# CPU_Logic.net
KiCad netlist of a schematic drawn in Altium Designer
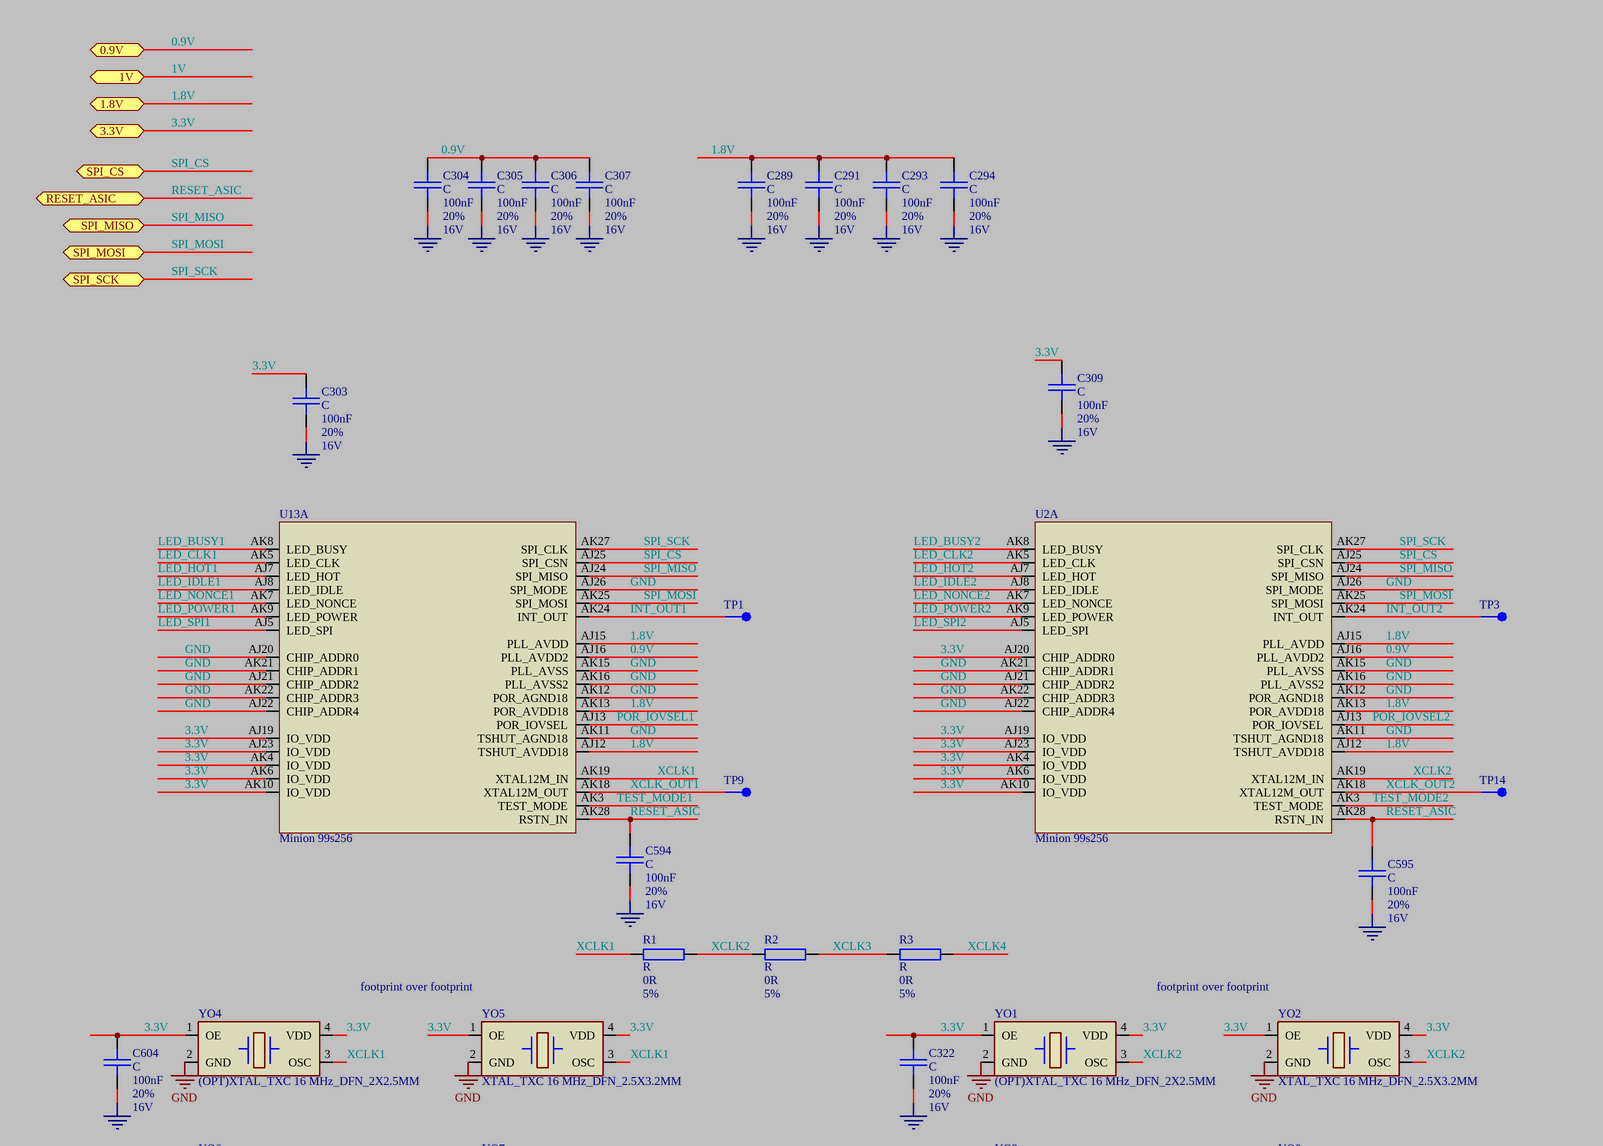
[diagram p0: CPU_Logic.SchDoc, top left]
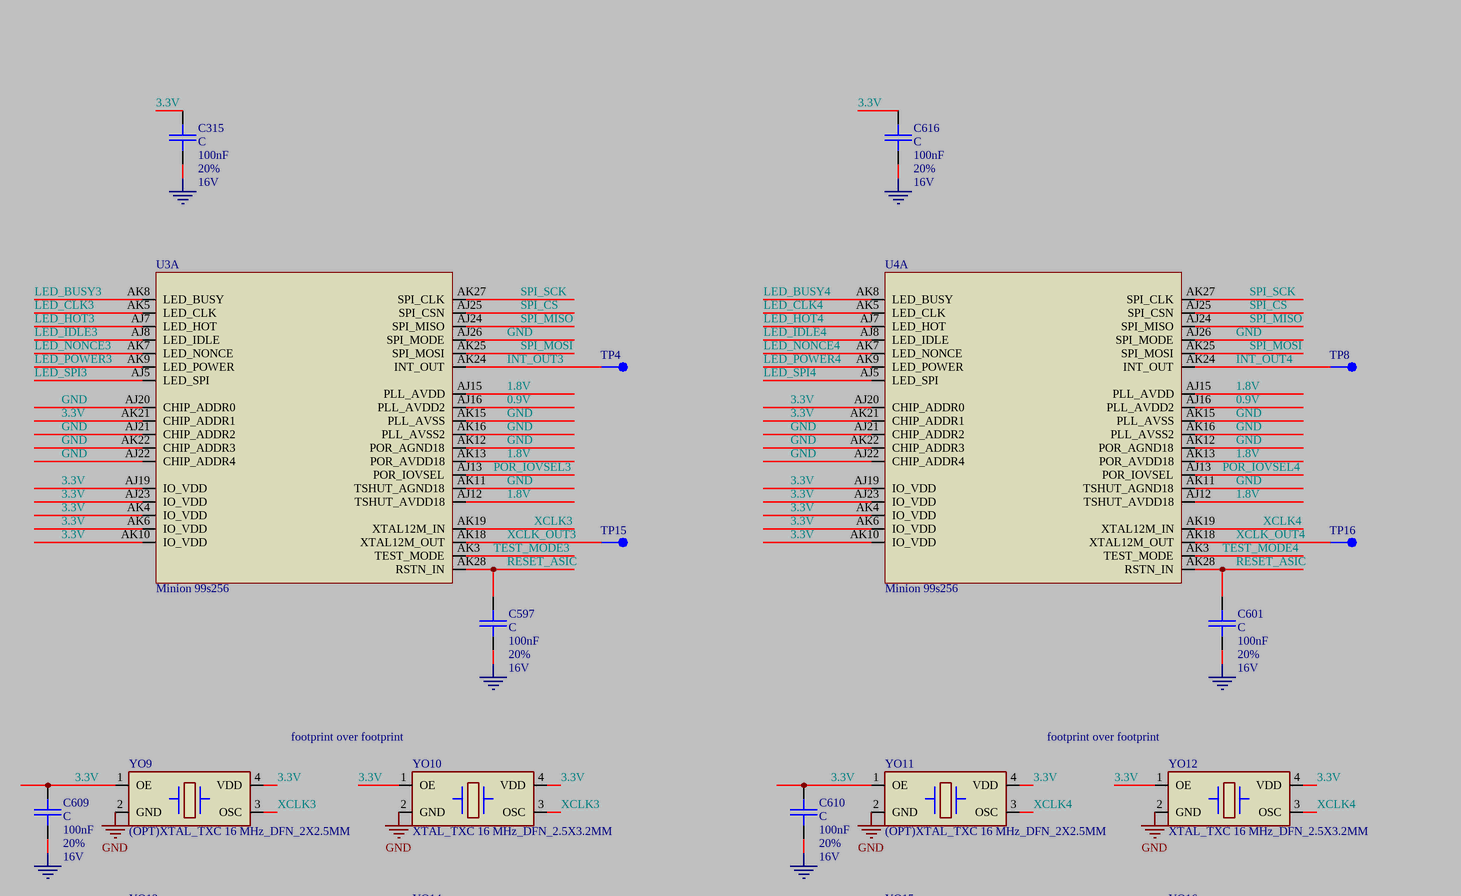
[diagram p1: CPU_Logic.SchDoc, top right]
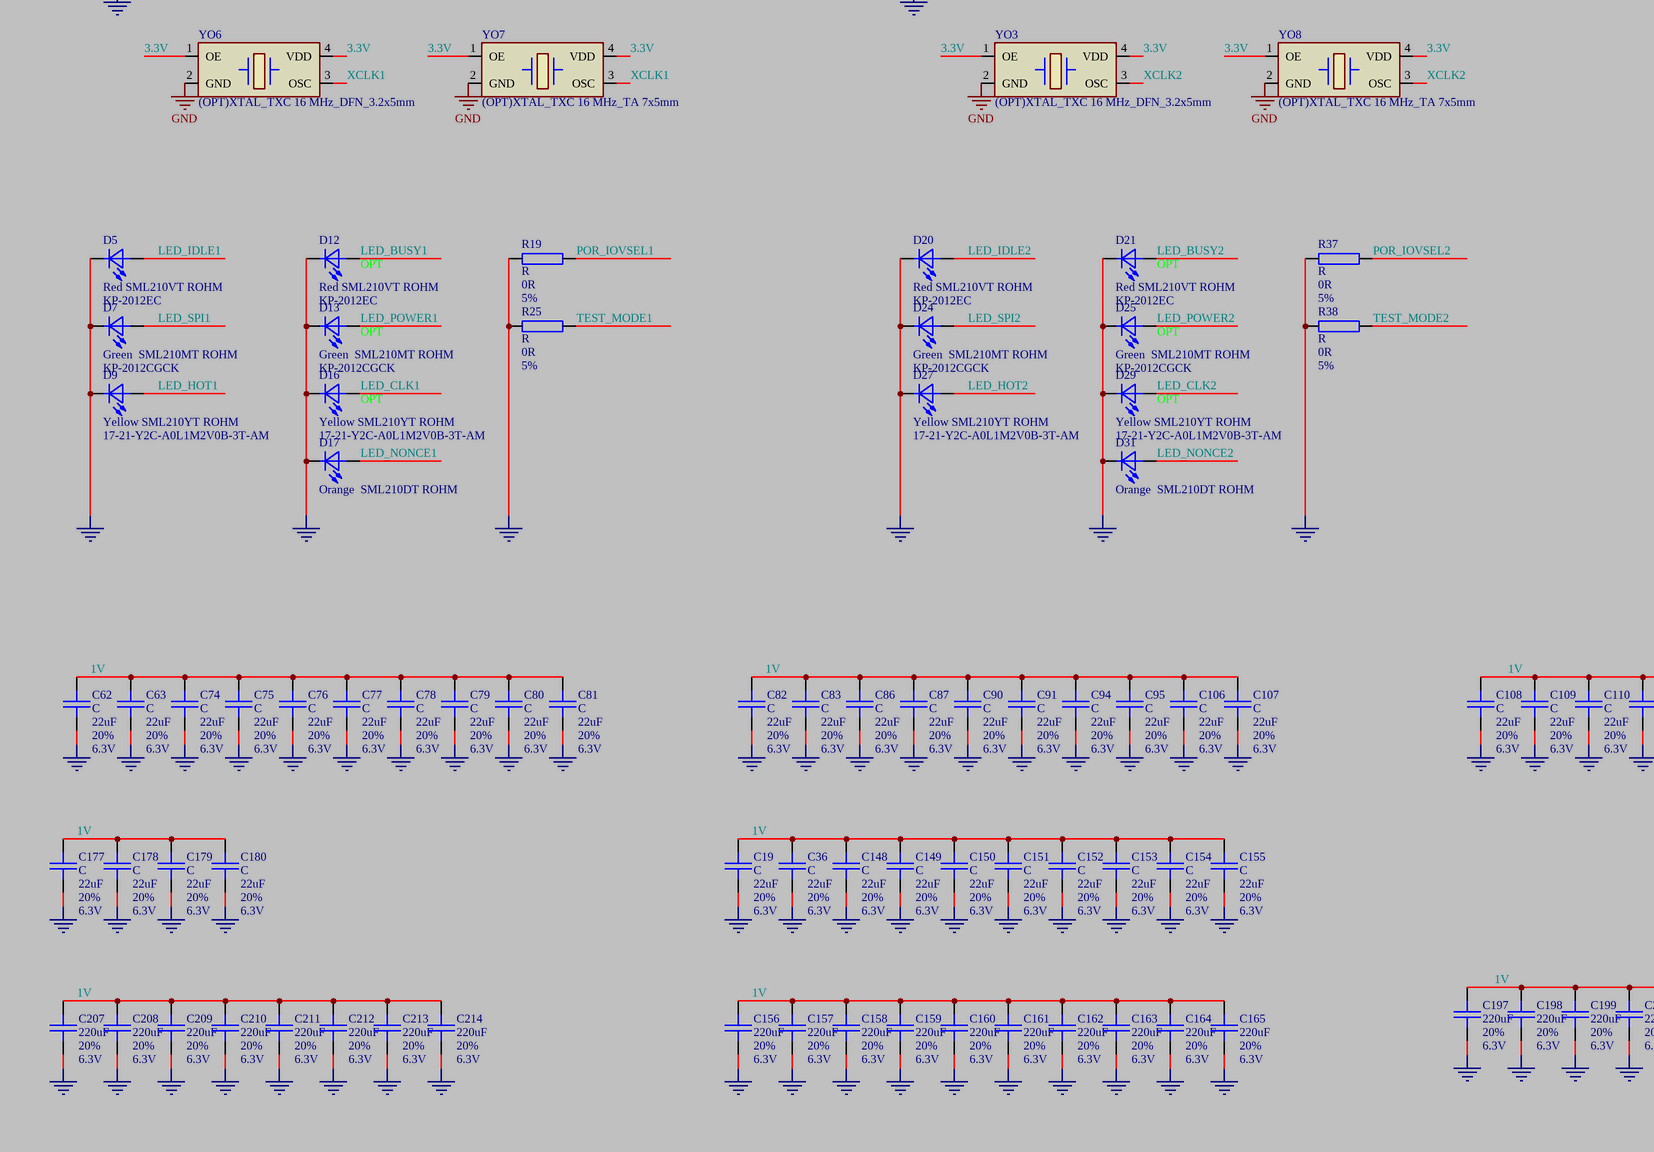
[diagram p2: CPU_Logic.SchDoc, bottom left]
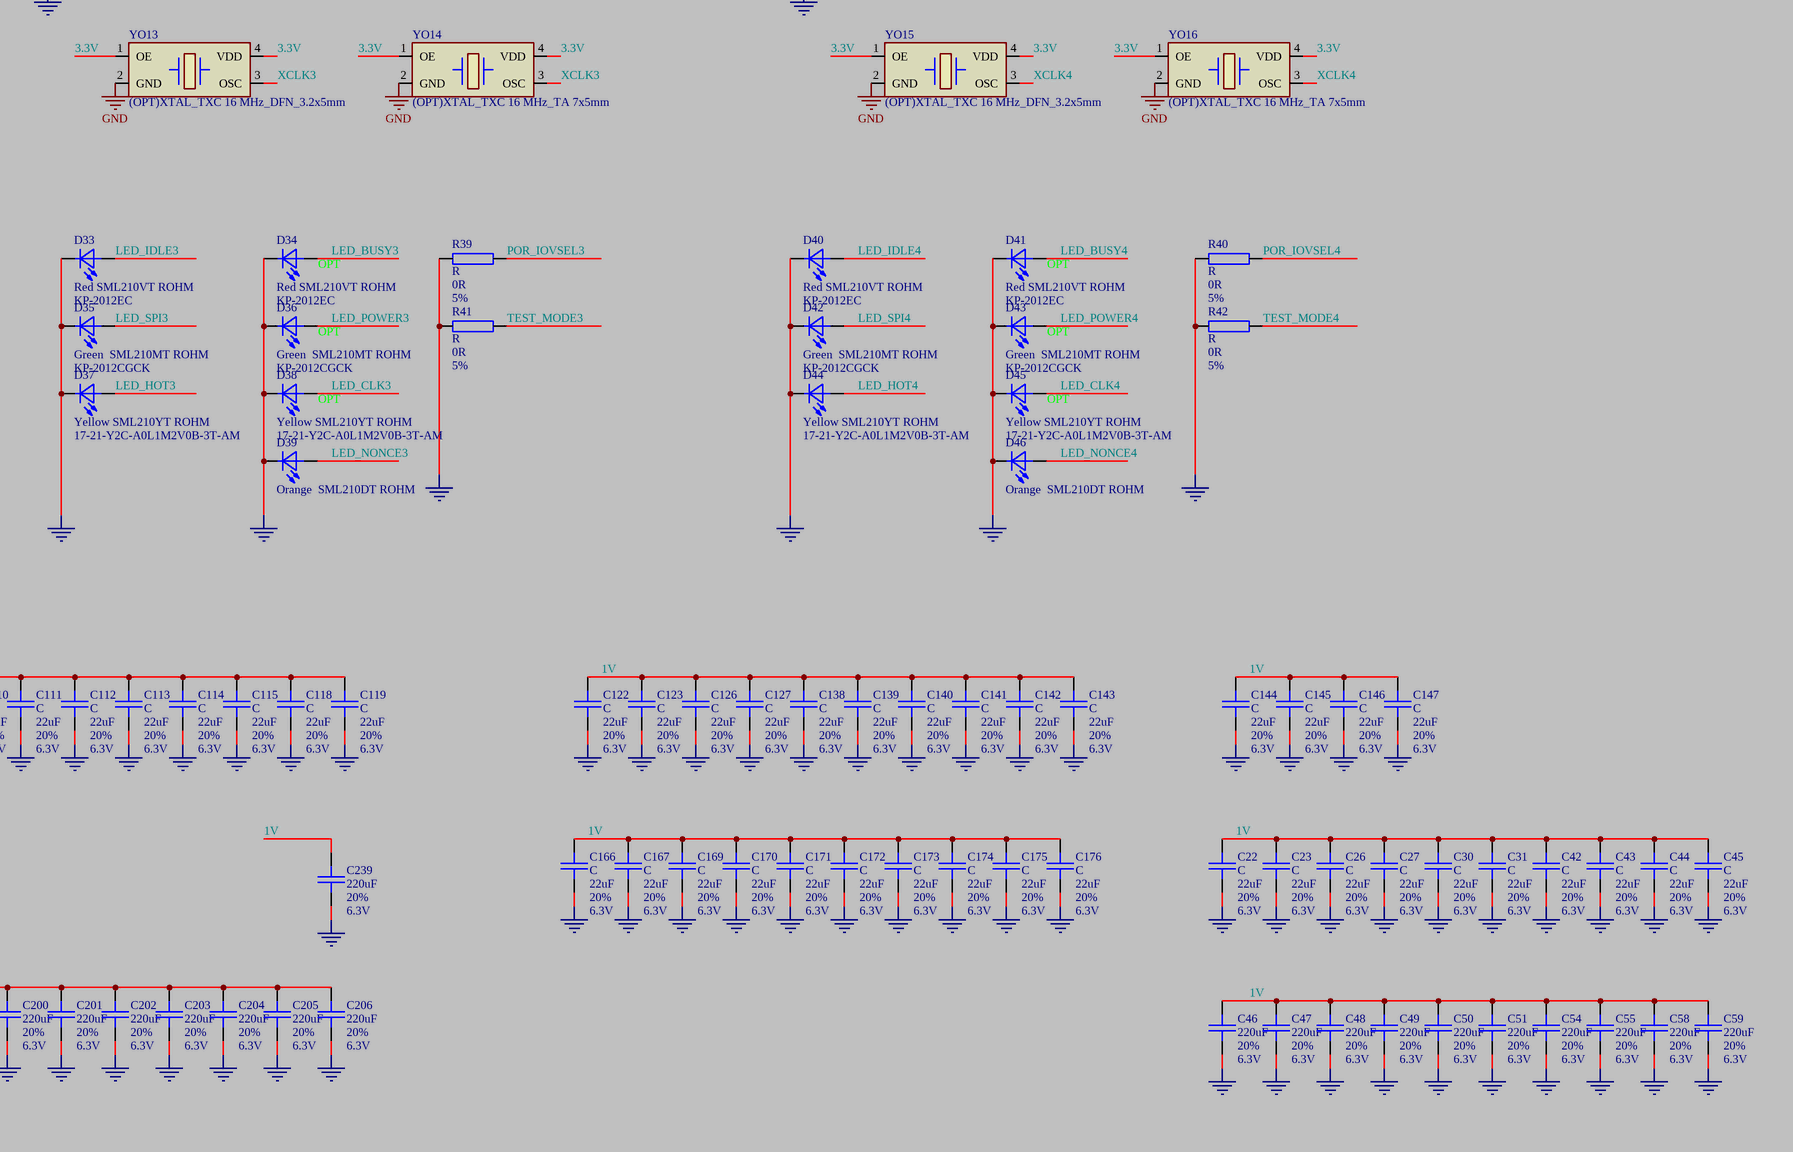
[diagram p3: CPU_Logic.SchDoc, bottom right]

(export (version "E")
  (design (tool "Eeschema 10.0.6"))
  (components
    (comp (ref "C19")
      (value "C")
      (footprint "SMD_0805_CAPC2012X145N")
      (fields
        (field (name "DB_PART_NUMBER") "CAP000043686")
        (field (name "DB_VALUE") "22uF")
        (field (name "DB_TOLERANCE") "20%")
        (field (name "DB_VOLTAGE") "6.3V")
        (field (name "DB_MANUFACTURER_PART") "KEMET    C0805C226M9PAC")
        (field (name "DB_APPROVED_BY") "ISHIDDEN=T")
      )
      (libsource (lib "Database_Libs1") (part "C"))
    )
    (comp (ref "C22")
      (value "C")
      (footprint "SMD_0805_CAPC2012X145N")
      (fields
        (field (name "DB_PART_NUMBER") "CAP000043686")
        (field (name "DB_VALUE") "22uF")
        (field (name "DB_TOLERANCE") "20%")
        (field (name "DB_VOLTAGE") "6.3V")
        (field (name "DB_MANUFACTURER_PART") "KEMET    C0805C226M9PAC")
        (field (name "DB_APPROVED_BY") "ISHIDDEN=T")
      )
      (libsource (lib "Database_Libs1") (part "C"))
    )
    (comp (ref "C23")
      (value "C")
      (footprint "SMD_0805_CAPC2012X145N")
      (fields
        (field (name "DB_PART_NUMBER") "CAP000043686")
        (field (name "DB_VALUE") "22uF")
        (field (name "DB_TOLERANCE") "20%")
        (field (name "DB_VOLTAGE") "6.3V")
        (field (name "DB_MANUFACTURER_PART") "KEMET    C0805C226M9PAC")
        (field (name "DB_APPROVED_BY") "ISHIDDEN=T")
      )
      (libsource (lib "Database_Libs1") (part "C"))
    )
    (comp (ref "C26")
      (value "C")
      (footprint "SMD_0805_CAPC2012X145N")
      (fields
        (field (name "DB_PART_NUMBER") "CAP000043686")
        (field (name "DB_VALUE") "22uF")
        (field (name "DB_TOLERANCE") "20%")
        (field (name "DB_VOLTAGE") "6.3V")
        (field (name "DB_MANUFACTURER_PART") "KEMET    C0805C226M9PAC")
        (field (name "DB_APPROVED_BY") "ISHIDDEN=T")
      )
      (libsource (lib "Database_Libs1") (part "C"))
    )
    (comp (ref "C27")
      (value "C")
      (footprint "SMD_0805_CAPC2012X145N")
      (fields
        (field (name "DB_PART_NUMBER") "CAP000043686")
        (field (name "DB_VALUE") "22uF")
        (field (name "DB_TOLERANCE") "20%")
        (field (name "DB_VOLTAGE") "6.3V")
        (field (name "DB_MANUFACTURER_PART") "KEMET    C0805C226M9PAC")
        (field (name "DB_APPROVED_BY") "ISHIDDEN=T")
      )
      (libsource (lib "Database_Libs1") (part "C"))
    )
    (comp (ref "C30")
      (value "C")
      (footprint "SMD_0805_CAPC2012X145N")
      (fields
        (field (name "DB_PART_NUMBER") "CAP000043686")
        (field (name "DB_VALUE") "22uF")
        (field (name "DB_TOLERANCE") "20%")
        (field (name "DB_VOLTAGE") "6.3V")
        (field (name "DB_MANUFACTURER_PART") "KEMET    C0805C226M9PAC")
        (field (name "DB_APPROVED_BY") "ISHIDDEN=T")
      )
      (libsource (lib "Database_Libs1") (part "C"))
    )
    (comp (ref "C31")
      (value "C")
      (footprint "SMD_0805_CAPC2012X145N")
      (fields
        (field (name "DB_PART_NUMBER") "CAP000043686")
        (field (name "DB_VALUE") "22uF")
        (field (name "DB_TOLERANCE") "20%")
        (field (name "DB_VOLTAGE") "6.3V")
        (field (name "DB_MANUFACTURER_PART") "KEMET    C0805C226M9PAC")
        (field (name "DB_APPROVED_BY") "ISHIDDEN=T")
      )
      (libsource (lib "Database_Libs1") (part "C"))
    )
    (comp (ref "C36")
      (value "C")
      (footprint "SMD_0805_CAPC2012X145N")
      (fields
        (field (name "DB_PART_NUMBER") "CAP000043686")
        (field (name "DB_VALUE") "22uF")
        (field (name "DB_TOLERANCE") "20%")
        (field (name "DB_VOLTAGE") "6.3V")
        (field (name "DB_MANUFACTURER_PART") "KEMET    C0805C226M9PAC")
        (field (name "DB_APPROVED_BY") "ISHIDDEN=T")
      )
      (libsource (lib "Database_Libs1") (part "C"))
    )
    (comp (ref "C42")
      (value "C")
      (footprint "SMD_0805_CAPC2012X145N")
      (fields
        (field (name "DB_PART_NUMBER") "CAP000043686")
        (field (name "DB_VALUE") "22uF")
        (field (name "DB_TOLERANCE") "20%")
        (field (name "DB_VOLTAGE") "6.3V")
        (field (name "DB_MANUFACTURER_PART") "KEMET    C0805C226M9PAC")
        (field (name "DB_APPROVED_BY") "ISHIDDEN=T")
      )
      (libsource (lib "Database_Libs1") (part "C"))
    )
    (comp (ref "C43")
      (value "C")
      (footprint "SMD_0805_CAPC2012X145N")
      (fields
        (field (name "DB_PART_NUMBER") "CAP000043686")
        (field (name "DB_VALUE") "22uF")
        (field (name "DB_TOLERANCE") "20%")
        (field (name "DB_VOLTAGE") "6.3V")
        (field (name "DB_MANUFACTURER_PART") "KEMET    C0805C226M9PAC")
        (field (name "DB_APPROVED_BY") "ISHIDDEN=T")
      )
      (libsource (lib "Database_Libs1") (part "C"))
    )
    (comp (ref "C44")
      (value "C")
      (footprint "SMD_0805_CAPC2012X145N")
      (fields
        (field (name "DB_PART_NUMBER") "CAP000043686")
        (field (name "DB_VALUE") "22uF")
        (field (name "DB_TOLERANCE") "20%")
        (field (name "DB_VOLTAGE") "6.3V")
        (field (name "DB_MANUFACTURER_PART") "KEMET    C0805C226M9PAC")
        (field (name "DB_APPROVED_BY") "ISHIDDEN=T")
      )
      (libsource (lib "Database_Libs1") (part "C"))
    )
    (comp (ref "C45")
      (value "C")
      (footprint "SMD_0805_CAPC2012X145N")
      (fields
        (field (name "DB_PART_NUMBER") "CAP000043686")
        (field (name "DB_VALUE") "22uF")
        (field (name "DB_TOLERANCE") "20%")
        (field (name "DB_VOLTAGE") "6.3V")
        (field (name "DB_MANUFACTURER_PART") "KEMET    C0805C226M9PAC")
        (field (name "DB_APPROVED_BY") "ISHIDDEN=T")
      )
      (libsource (lib "Database_Libs1") (part "C"))
    )
    (comp (ref "C46")
      (value "C")
      (footprint "SMD_1210_CAPC3225X279N")
      (fields
        (field (name "DB_PART_NUMBER") "CAP000047355")
        (field (name "DB_VALUE") "220uF")
        (field (name "DB_TOLERANCE") "20%")
        (field (name "DB_VOLTAGE") "6.3V")
        (field (name "DB_MANUFACTURER_PART") "SAMSUNG    CL32A227MQVNNNE")
        (field (name "DB_APPROVED_BY") "VSN")
      )
      (libsource (lib "Database_Libs1") (part "C"))
    )
    (comp (ref "C47")
      (value "C")
      (footprint "SMD_1210_CAPC3225X279N")
      (fields
        (field (name "DB_PART_NUMBER") "CAP000047355")
        (field (name "DB_VALUE") "220uF")
        (field (name "DB_TOLERANCE") "20%")
        (field (name "DB_VOLTAGE") "6.3V")
        (field (name "DB_MANUFACTURER_PART") "SAMSUNG    CL32A227MQVNNNE")
        (field (name "DB_APPROVED_BY") "VSN")
      )
      (libsource (lib "Database_Libs1") (part "C"))
    )
    (comp (ref "C48")
      (value "C")
      (footprint "SMD_1210_CAPC3225X279N")
      (fields
        (field (name "DB_PART_NUMBER") "CAP000047355")
        (field (name "DB_VALUE") "220uF")
        (field (name "DB_TOLERANCE") "20%")
        (field (name "DB_VOLTAGE") "6.3V")
        (field (name "DB_MANUFACTURER_PART") "SAMSUNG    CL32A227MQVNNNE")
        (field (name "DB_APPROVED_BY") "VSN")
      )
      (libsource (lib "Database_Libs1") (part "C"))
    )
    (comp (ref "C49")
      (value "C")
      (footprint "SMD_1210_CAPC3225X279N")
      (fields
        (field (name "DB_PART_NUMBER") "CAP000047355")
        (field (name "DB_VALUE") "220uF")
        (field (name "DB_TOLERANCE") "20%")
        (field (name "DB_VOLTAGE") "6.3V")
        (field (name "DB_MANUFACTURER_PART") "SAMSUNG    CL32A227MQVNNNE")
        (field (name "DB_APPROVED_BY") "VSN")
      )
      (libsource (lib "Database_Libs1") (part "C"))
    )
    (comp (ref "C50")
      (value "C")
      (footprint "SMD_1210_CAPC3225X279N")
      (fields
        (field (name "DB_PART_NUMBER") "CAP000047355")
        (field (name "DB_VALUE") "220uF")
        (field (name "DB_TOLERANCE") "20%")
        (field (name "DB_VOLTAGE") "6.3V")
        (field (name "DB_MANUFACTURER_PART") "SAMSUNG    CL32A227MQVNNNE")
        (field (name "DB_APPROVED_BY") "VSN")
      )
      (libsource (lib "Database_Libs1") (part "C"))
    )
    (comp (ref "C51")
      (value "C")
      (footprint "SMD_1210_CAPC3225X279N")
      (fields
        (field (name "DB_PART_NUMBER") "CAP000047355")
        (field (name "DB_VALUE") "220uF")
        (field (name "DB_TOLERANCE") "20%")
        (field (name "DB_VOLTAGE") "6.3V")
        (field (name "DB_MANUFACTURER_PART") "SAMSUNG    CL32A227MQVNNNE")
        (field (name "DB_APPROVED_BY") "VSN")
      )
      (libsource (lib "Database_Libs1") (part "C"))
    )
    (comp (ref "C54")
      (value "C")
      (footprint "SMD_1210_CAPC3225X279N")
      (fields
        (field (name "DB_PART_NUMBER") "CAP000047355")
        (field (name "DB_VALUE") "220uF")
        (field (name "DB_TOLERANCE") "20%")
        (field (name "DB_VOLTAGE") "6.3V")
        (field (name "DB_MANUFACTURER_PART") "SAMSUNG    CL32A227MQVNNNE")
        (field (name "DB_APPROVED_BY") "VSN")
      )
      (libsource (lib "Database_Libs1") (part "C"))
    )
    (comp (ref "C55")
      (value "C")
      (footprint "SMD_1210_CAPC3225X279N")
      (fields
        (field (name "DB_PART_NUMBER") "CAP000047355")
        (field (name "DB_VALUE") "220uF")
        (field (name "DB_TOLERANCE") "20%")
        (field (name "DB_VOLTAGE") "6.3V")
        (field (name "DB_MANUFACTURER_PART") "SAMSUNG    CL32A227MQVNNNE")
        (field (name "DB_APPROVED_BY") "VSN")
      )
      (libsource (lib "Database_Libs1") (part "C"))
    )
    (comp (ref "C58")
      (value "C")
      (footprint "SMD_1210_CAPC3225X279N")
      (fields
        (field (name "DB_PART_NUMBER") "CAP000047355")
        (field (name "DB_VALUE") "220uF")
        (field (name "DB_TOLERANCE") "20%")
        (field (name "DB_VOLTAGE") "6.3V")
        (field (name "DB_MANUFACTURER_PART") "SAMSUNG    CL32A227MQVNNNE")
        (field (name "DB_APPROVED_BY") "VSN")
      )
      (libsource (lib "Database_Libs1") (part "C"))
    )
    (comp (ref "C59")
      (value "C")
      (footprint "SMD_1210_CAPC3225X279N")
      (fields
        (field (name "DB_PART_NUMBER") "CAP000047355")
        (field (name "DB_VALUE") "220uF")
        (field (name "DB_TOLERANCE") "20%")
        (field (name "DB_VOLTAGE") "6.3V")
        (field (name "DB_MANUFACTURER_PART") "SAMSUNG    CL32A227MQVNNNE")
        (field (name "DB_APPROVED_BY") "VSN")
      )
      (libsource (lib "Database_Libs1") (part "C"))
    )
    (comp (ref "C62")
      (value "C")
      (footprint "SMD_0805_CAPC2012X145N")
      (fields
        (field (name "DB_PART_NUMBER") "CAP000043686")
        (field (name "DB_VALUE") "22uF")
        (field (name "DB_TOLERANCE") "20%")
        (field (name "DB_VOLTAGE") "6.3V")
        (field (name "DB_MANUFACTURER_PART") "KEMET    C0805C226M9PAC")
        (field (name "DB_APPROVED_BY") "ISHIDDEN=T")
      )
      (libsource (lib "Database_Libs1") (part "C"))
    )
    (comp (ref "C63")
      (value "C")
      (footprint "SMD_0805_CAPC2012X145N")
      (fields
        (field (name "DB_PART_NUMBER") "CAP000043686")
        (field (name "DB_VALUE") "22uF")
        (field (name "DB_TOLERANCE") "20%")
        (field (name "DB_VOLTAGE") "6.3V")
        (field (name "DB_MANUFACTURER_PART") "KEMET    C0805C226M9PAC")
        (field (name "DB_APPROVED_BY") "ISHIDDEN=T")
      )
      (libsource (lib "Database_Libs1") (part "C"))
    )
    (comp (ref "C74")
      (value "C")
      (footprint "SMD_0805_CAPC2012X145N")
      (fields
        (field (name "DB_PART_NUMBER") "CAP000043686")
        (field (name "DB_VALUE") "22uF")
        (field (name "DB_TOLERANCE") "20%")
        (field (name "DB_VOLTAGE") "6.3V")
        (field (name "DB_MANUFACTURER_PART") "KEMET    C0805C226M9PAC")
        (field (name "DB_APPROVED_BY") "ISHIDDEN=T")
      )
      (libsource (lib "Database_Libs1") (part "C"))
    )
    (comp (ref "C75")
      (value "C")
      (footprint "SMD_0805_CAPC2012X145N")
      (fields
        (field (name "DB_PART_NUMBER") "CAP000043686")
        (field (name "DB_VALUE") "22uF")
        (field (name "DB_TOLERANCE") "20%")
        (field (name "DB_VOLTAGE") "6.3V")
        (field (name "DB_MANUFACTURER_PART") "KEMET    C0805C226M9PAC")
        (field (name "DB_APPROVED_BY") "ISHIDDEN=T")
      )
      (libsource (lib "Database_Libs1") (part "C"))
    )
    (comp (ref "C76")
      (value "C")
      (footprint "SMD_0805_CAPC2012X145N")
      (fields
        (field (name "DB_PART_NUMBER") "CAP000043686")
        (field (name "DB_VALUE") "22uF")
        (field (name "DB_TOLERANCE") "20%")
        (field (name "DB_VOLTAGE") "6.3V")
        (field (name "DB_MANUFACTURER_PART") "KEMET    C0805C226M9PAC")
        (field (name "DB_APPROVED_BY") "ISHIDDEN=T")
      )
      (libsource (lib "Database_Libs1") (part "C"))
    )
    (comp (ref "C77")
      (value "C")
      (footprint "SMD_0805_CAPC2012X145N")
      (fields
        (field (name "DB_PART_NUMBER") "CAP000043686")
        (field (name "DB_VALUE") "22uF")
        (field (name "DB_TOLERANCE") "20%")
        (field (name "DB_VOLTAGE") "6.3V")
        (field (name "DB_MANUFACTURER_PART") "KEMET    C0805C226M9PAC")
        (field (name "DB_APPROVED_BY") "ISHIDDEN=T")
      )
      (libsource (lib "Database_Libs1") (part "C"))
    )
    (comp (ref "C78")
      (value "C")
      (footprint "SMD_0805_CAPC2012X145N")
      (fields
        (field (name "DB_PART_NUMBER") "CAP000043686")
        (field (name "DB_VALUE") "22uF")
        (field (name "DB_TOLERANCE") "20%")
        (field (name "DB_VOLTAGE") "6.3V")
        (field (name "DB_MANUFACTURER_PART") "KEMET    C0805C226M9PAC")
        (field (name "DB_APPROVED_BY") "ISHIDDEN=T")
      )
      (libsource (lib "Database_Libs1") (part "C"))
    )
    (comp (ref "C79")
      (value "C")
      (footprint "SMD_0805_CAPC2012X145N")
      (fields
        (field (name "DB_PART_NUMBER") "CAP000043686")
        (field (name "DB_VALUE") "22uF")
        (field (name "DB_TOLERANCE") "20%")
        (field (name "DB_VOLTAGE") "6.3V")
        (field (name "DB_MANUFACTURER_PART") "KEMET    C0805C226M9PAC")
        (field (name "DB_APPROVED_BY") "ISHIDDEN=T")
      )
      (libsource (lib "Database_Libs1") (part "C"))
    )
    (comp (ref "C80")
      (value "C")
      (footprint "SMD_0805_CAPC2012X145N")
      (fields
        (field (name "DB_PART_NUMBER") "CAP000043686")
        (field (name "DB_VALUE") "22uF")
        (field (name "DB_TOLERANCE") "20%")
        (field (name "DB_VOLTAGE") "6.3V")
        (field (name "DB_MANUFACTURER_PART") "KEMET    C0805C226M9PAC")
        (field (name "DB_APPROVED_BY") "ISHIDDEN=T")
      )
      (libsource (lib "Database_Libs1") (part "C"))
    )
    (comp (ref "C81")
      (value "C")
      (footprint "SMD_0805_CAPC2012X145N")
      (fields
        (field (name "DB_PART_NUMBER") "CAP000043686")
        (field (name "DB_VALUE") "22uF")
        (field (name "DB_TOLERANCE") "20%")
        (field (name "DB_VOLTAGE") "6.3V")
        (field (name "DB_MANUFACTURER_PART") "KEMET    C0805C226M9PAC")
        (field (name "DB_APPROVED_BY") "ISHIDDEN=T")
      )
      (libsource (lib "Database_Libs1") (part "C"))
    )
    (comp (ref "C82")
      (value "C")
      (footprint "SMD_0805_CAPC2012X145N")
      (fields
        (field (name "DB_PART_NUMBER") "CAP000043686")
        (field (name "DB_VALUE") "22uF")
        (field (name "DB_TOLERANCE") "20%")
        (field (name "DB_VOLTAGE") "6.3V")
        (field (name "DB_MANUFACTURER_PART") "KEMET    C0805C226M9PAC")
        (field (name "DB_APPROVED_BY") "ISHIDDEN=T")
      )
      (libsource (lib "Database_Libs1") (part "C"))
    )
    (comp (ref "C83")
      (value "C")
      (footprint "SMD_0805_CAPC2012X145N")
      (fields
        (field (name "DB_PART_NUMBER") "CAP000043686")
        (field (name "DB_VALUE") "22uF")
        (field (name "DB_TOLERANCE") "20%")
        (field (name "DB_VOLTAGE") "6.3V")
        (field (name "DB_MANUFACTURER_PART") "KEMET    C0805C226M9PAC")
        (field (name "DB_APPROVED_BY") "ISHIDDEN=T")
      )
      (libsource (lib "Database_Libs1") (part "C"))
    )
    (comp (ref "C86")
      (value "C")
      (footprint "SMD_0805_CAPC2012X145N")
      (fields
        (field (name "DB_PART_NUMBER") "CAP000043686")
        (field (name "DB_VALUE") "22uF")
        (field (name "DB_TOLERANCE") "20%")
        (field (name "DB_VOLTAGE") "6.3V")
        (field (name "DB_MANUFACTURER_PART") "KEMET    C0805C226M9PAC")
        (field (name "DB_APPROVED_BY") "ISHIDDEN=T")
      )
      (libsource (lib "Database_Libs1") (part "C"))
    )
    (comp (ref "C87")
      (value "C")
      (footprint "SMD_0805_CAPC2012X145N")
      (fields
        (field (name "DB_PART_NUMBER") "CAP000043686")
        (field (name "DB_VALUE") "22uF")
        (field (name "DB_TOLERANCE") "20%")
        (field (name "DB_VOLTAGE") "6.3V")
        (field (name "DB_MANUFACTURER_PART") "KEMET    C0805C226M9PAC")
        (field (name "DB_APPROVED_BY") "ISHIDDEN=T")
      )
      (libsource (lib "Database_Libs1") (part "C"))
    )
    (comp (ref "C90")
      (value "C")
      (footprint "SMD_0805_CAPC2012X145N")
      (fields
        (field (name "DB_PART_NUMBER") "CAP000043686")
        (field (name "DB_VALUE") "22uF")
        (field (name "DB_TOLERANCE") "20%")
        (field (name "DB_VOLTAGE") "6.3V")
        (field (name "DB_MANUFACTURER_PART") "KEMET    C0805C226M9PAC")
        (field (name "DB_APPROVED_BY") "ISHIDDEN=T")
      )
      (libsource (lib "Database_Libs1") (part "C"))
    )
    (comp (ref "C91")
      (value "C")
      (footprint "SMD_0805_CAPC2012X145N")
      (fields
        (field (name "DB_PART_NUMBER") "CAP000043686")
        (field (name "DB_VALUE") "22uF")
        (field (name "DB_TOLERANCE") "20%")
        (field (name "DB_VOLTAGE") "6.3V")
        (field (name "DB_MANUFACTURER_PART") "KEMET    C0805C226M9PAC")
        (field (name "DB_APPROVED_BY") "ISHIDDEN=T")
      )
      (libsource (lib "Database_Libs1") (part "C"))
    )
    (comp (ref "C94")
      (value "C")
      (footprint "SMD_0805_CAPC2012X145N")
      (fields
        (field (name "DB_PART_NUMBER") "CAP000043686")
        (field (name "DB_VALUE") "22uF")
        (field (name "DB_TOLERANCE") "20%")
        (field (name "DB_VOLTAGE") "6.3V")
        (field (name "DB_MANUFACTURER_PART") "KEMET    C0805C226M9PAC")
        (field (name "DB_APPROVED_BY") "ISHIDDEN=T")
      )
      (libsource (lib "Database_Libs1") (part "C"))
    )
    (comp (ref "C95")
      (value "C")
      (footprint "SMD_0805_CAPC2012X145N")
      (fields
        (field (name "DB_PART_NUMBER") "CAP000043686")
        (field (name "DB_VALUE") "22uF")
        (field (name "DB_TOLERANCE") "20%")
        (field (name "DB_VOLTAGE") "6.3V")
        (field (name "DB_MANUFACTURER_PART") "KEMET    C0805C226M9PAC")
        (field (name "DB_APPROVED_BY") "ISHIDDEN=T")
      )
      (libsource (lib "Database_Libs1") (part "C"))
    )
    (comp (ref "C106")
      (value "C")
      (footprint "SMD_0805_CAPC2012X145N")
      (fields
        (field (name "DB_PART_NUMBER") "CAP000043686")
        (field (name "DB_VALUE") "22uF")
        (field (name "DB_TOLERANCE") "20%")
        (field (name "DB_VOLTAGE") "6.3V")
        (field (name "DB_MANUFACTURER_PART") "KEMET    C0805C226M9PAC")
        (field (name "DB_APPROVED_BY") "ISHIDDEN=T")
      )
      (libsource (lib "Database_Libs1") (part "C"))
    )
    (comp (ref "C107")
      (value "C")
      (footprint "SMD_0805_CAPC2012X145N")
      (fields
        (field (name "DB_PART_NUMBER") "CAP000043686")
        (field (name "DB_VALUE") "22uF")
        (field (name "DB_TOLERANCE") "20%")
        (field (name "DB_VOLTAGE") "6.3V")
        (field (name "DB_MANUFACTURER_PART") "KEMET    C0805C226M9PAC")
        (field (name "DB_APPROVED_BY") "ISHIDDEN=T")
      )
      (libsource (lib "Database_Libs1") (part "C"))
    )
    (comp (ref "C108")
      (value "C")
      (footprint "SMD_0805_CAPC2012X145N")
      (fields
        (field (name "DB_PART_NUMBER") "CAP000043686")
        (field (name "DB_VALUE") "22uF")
        (field (name "DB_TOLERANCE") "20%")
        (field (name "DB_VOLTAGE") "6.3V")
        (field (name "DB_MANUFACTURER_PART") "KEMET    C0805C226M9PAC")
        (field (name "DB_APPROVED_BY") "ISHIDDEN=T")
      )
      (libsource (lib "Database_Libs1") (part "C"))
    )
    (comp (ref "C109")
      (value "C")
      (footprint "SMD_0805_CAPC2012X145N")
      (fields
        (field (name "DB_PART_NUMBER") "CAP000043686")
        (field (name "DB_VALUE") "22uF")
        (field (name "DB_TOLERANCE") "20%")
        (field (name "DB_VOLTAGE") "6.3V")
        (field (name "DB_MANUFACTURER_PART") "KEMET    C0805C226M9PAC")
        (field (name "DB_APPROVED_BY") "ISHIDDEN=T")
      )
      (libsource (lib "Database_Libs1") (part "C"))
    )
    (comp (ref "C110")
      (value "C")
      (footprint "SMD_0805_CAPC2012X145N")
      (fields
        (field (name "DB_PART_NUMBER") "CAP000043686")
        (field (name "DB_VALUE") "22uF")
        (field (name "DB_TOLERANCE") "20%")
        (field (name "DB_VOLTAGE") "6.3V")
        (field (name "DB_MANUFACTURER_PART") "KEMET    C0805C226M9PAC")
        (field (name "DB_APPROVED_BY") "ISHIDDEN=T")
      )
      (libsource (lib "Database_Libs1") (part "C"))
    )
    (comp (ref "C111")
      (value "C")
      (footprint "SMD_0805_CAPC2012X145N")
      (fields
        (field (name "DB_PART_NUMBER") "CAP000043686")
        (field (name "DB_VALUE") "22uF")
        (field (name "DB_TOLERANCE") "20%")
        (field (name "DB_VOLTAGE") "6.3V")
        (field (name "DB_MANUFACTURER_PART") "KEMET    C0805C226M9PAC")
        (field (name "DB_APPROVED_BY") "ISHIDDEN=T")
      )
      (libsource (lib "Database_Libs1") (part "C"))
    )
    (comp (ref "C112")
      (value "C")
      (footprint "SMD_0805_CAPC2012X145N")
      (fields
        (field (name "DB_PART_NUMBER") "CAP000043686")
        (field (name "DB_VALUE") "22uF")
        (field (name "DB_TOLERANCE") "20%")
        (field (name "DB_VOLTAGE") "6.3V")
        (field (name "DB_MANUFACTURER_PART") "KEMET    C0805C226M9PAC")
        (field (name "DB_APPROVED_BY") "ISHIDDEN=T")
      )
      (libsource (lib "Database_Libs1") (part "C"))
    )
    (comp (ref "C113")
      (value "C")
      (footprint "SMD_0805_CAPC2012X145N")
      (fields
        (field (name "DB_PART_NUMBER") "CAP000043686")
        (field (name "DB_VALUE") "22uF")
        (field (name "DB_TOLERANCE") "20%")
        (field (name "DB_VOLTAGE") "6.3V")
        (field (name "DB_MANUFACTURER_PART") "KEMET    C0805C226M9PAC")
        (field (name "DB_APPROVED_BY") "ISHIDDEN=T")
      )
      (libsource (lib "Database_Libs1") (part "C"))
    )
    (comp (ref "C114")
      (value "C")
      (footprint "SMD_0805_CAPC2012X145N")
      (fields
        (field (name "DB_PART_NUMBER") "CAP000043686")
        (field (name "DB_VALUE") "22uF")
        (field (name "DB_TOLERANCE") "20%")
        (field (name "DB_VOLTAGE") "6.3V")
        (field (name "DB_MANUFACTURER_PART") "KEMET    C0805C226M9PAC")
        (field (name "DB_APPROVED_BY") "ISHIDDEN=T")
      )
      (libsource (lib "Database_Libs1") (part "C"))
    )
    (comp (ref "C115")
      (value "C")
      (footprint "SMD_0805_CAPC2012X145N")
      (fields
        (field (name "DB_PART_NUMBER") "CAP000043686")
        (field (name "DB_VALUE") "22uF")
        (field (name "DB_TOLERANCE") "20%")
        (field (name "DB_VOLTAGE") "6.3V")
        (field (name "DB_MANUFACTURER_PART") "KEMET    C0805C226M9PAC")
        (field (name "DB_APPROVED_BY") "ISHIDDEN=T")
      )
      (libsource (lib "Database_Libs1") (part "C"))
    )
    (comp (ref "C118")
      (value "C")
      (footprint "SMD_0805_CAPC2012X145N")
      (fields
        (field (name "DB_PART_NUMBER") "CAP000043686")
        (field (name "DB_VALUE") "22uF")
        (field (name "DB_TOLERANCE") "20%")
        (field (name "DB_VOLTAGE") "6.3V")
        (field (name "DB_MANUFACTURER_PART") "KEMET    C0805C226M9PAC")
        (field (name "DB_APPROVED_BY") "ISHIDDEN=T")
      )
      (libsource (lib "Database_Libs1") (part "C"))
    )
    (comp (ref "C119")
      (value "C")
      (footprint "SMD_0805_CAPC2012X145N")
      (fields
        (field (name "DB_PART_NUMBER") "CAP000043686")
        (field (name "DB_VALUE") "22uF")
        (field (name "DB_TOLERANCE") "20%")
        (field (name "DB_VOLTAGE") "6.3V")
        (field (name "DB_MANUFACTURER_PART") "KEMET    C0805C226M9PAC")
        (field (name "DB_APPROVED_BY") "ISHIDDEN=T")
      )
      (libsource (lib "Database_Libs1") (part "C"))
    )
    (comp (ref "C122")
      (value "C")
      (footprint "SMD_0805_CAPC2012X145N")
      (fields
        (field (name "DB_PART_NUMBER") "CAP000043686")
        (field (name "DB_VALUE") "22uF")
        (field (name "DB_TOLERANCE") "20%")
        (field (name "DB_VOLTAGE") "6.3V")
        (field (name "DB_MANUFACTURER_PART") "KEMET    C0805C226M9PAC")
        (field (name "DB_APPROVED_BY") "ISHIDDEN=T")
      )
      (libsource (lib "Database_Libs1") (part "C"))
    )
    (comp (ref "C123")
      (value "C")
      (footprint "SMD_0805_CAPC2012X145N")
      (fields
        (field (name "DB_PART_NUMBER") "CAP000043686")
        (field (name "DB_VALUE") "22uF")
        (field (name "DB_TOLERANCE") "20%")
        (field (name "DB_VOLTAGE") "6.3V")
        (field (name "DB_MANUFACTURER_PART") "KEMET    C0805C226M9PAC")
        (field (name "DB_APPROVED_BY") "ISHIDDEN=T")
      )
      (libsource (lib "Database_Libs1") (part "C"))
    )
    (comp (ref "C126")
      (value "C")
      (footprint "SMD_0805_CAPC2012X145N")
      (fields
        (field (name "DB_PART_NUMBER") "CAP000043686")
        (field (name "DB_VALUE") "22uF")
        (field (name "DB_TOLERANCE") "20%")
        (field (name "DB_VOLTAGE") "6.3V")
        (field (name "DB_MANUFACTURER_PART") "KEMET    C0805C226M9PAC")
        (field (name "DB_APPROVED_BY") "ISHIDDEN=T")
      )
      (libsource (lib "Database_Libs1") (part "C"))
    )
    (comp (ref "C127")
      (value "C")
      (footprint "SMD_0805_CAPC2012X145N")
      (fields
        (field (name "DB_PART_NUMBER") "CAP000043686")
        (field (name "DB_VALUE") "22uF")
        (field (name "DB_TOLERANCE") "20%")
        (field (name "DB_VOLTAGE") "6.3V")
        (field (name "DB_MANUFACTURER_PART") "KEMET    C0805C226M9PAC")
        (field (name "DB_APPROVED_BY") "ISHIDDEN=T")
      )
      (libsource (lib "Database_Libs1") (part "C"))
    )
    (comp (ref "C138")
      (value "C")
      (footprint "SMD_0805_CAPC2012X145N")
      (fields
        (field (name "DB_PART_NUMBER") "CAP000043686")
        (field (name "DB_VALUE") "22uF")
        (field (name "DB_TOLERANCE") "20%")
        (field (name "DB_VOLTAGE") "6.3V")
        (field (name "DB_MANUFACTURER_PART") "KEMET    C0805C226M9PAC")
        (field (name "DB_APPROVED_BY") "ISHIDDEN=T")
      )
      (libsource (lib "Database_Libs1") (part "C"))
    )
    (comp (ref "C139")
      (value "C")
      (footprint "SMD_0805_CAPC2012X145N")
      (fields
        (field (name "DB_PART_NUMBER") "CAP000043686")
        (field (name "DB_VALUE") "22uF")
        (field (name "DB_TOLERANCE") "20%")
        (field (name "DB_VOLTAGE") "6.3V")
        (field (name "DB_MANUFACTURER_PART") "KEMET    C0805C226M9PAC")
        (field (name "DB_APPROVED_BY") "ISHIDDEN=T")
      )
      (libsource (lib "Database_Libs1") (part "C"))
    )
    (comp (ref "C140")
      (value "C")
      (footprint "SMD_0805_CAPC2012X145N")
      (fields
        (field (name "DB_PART_NUMBER") "CAP000043686")
        (field (name "DB_VALUE") "22uF")
        (field (name "DB_TOLERANCE") "20%")
        (field (name "DB_VOLTAGE") "6.3V")
        (field (name "DB_MANUFACTURER_PART") "KEMET    C0805C226M9PAC")
        (field (name "DB_APPROVED_BY") "ISHIDDEN=T")
      )
      (libsource (lib "Database_Libs1") (part "C"))
    )
    (comp (ref "C141")
      (value "C")
      (footprint "SMD_0805_CAPC2012X145N")
      (fields
        (field (name "DB_PART_NUMBER") "CAP000043686")
        (field (name "DB_VALUE") "22uF")
        (field (name "DB_TOLERANCE") "20%")
        (field (name "DB_VOLTAGE") "6.3V")
        (field (name "DB_MANUFACTURER_PART") "KEMET    C0805C226M9PAC")
        (field (name "DB_APPROVED_BY") "ISHIDDEN=T")
      )
      (libsource (lib "Database_Libs1") (part "C"))
    )
    (comp (ref "C142")
      (value "C")
      (footprint "SMD_0805_CAPC2012X145N")
      (fields
        (field (name "DB_PART_NUMBER") "CAP000043686")
        (field (name "DB_VALUE") "22uF")
        (field (name "DB_TOLERANCE") "20%")
        (field (name "DB_VOLTAGE") "6.3V")
        (field (name "DB_MANUFACTURER_PART") "KEMET    C0805C226M9PAC")
        (field (name "DB_APPROVED_BY") "ISHIDDEN=T")
      )
      (libsource (lib "Database_Libs1") (part "C"))
    )
    (comp (ref "C143")
      (value "C")
      (footprint "SMD_0805_CAPC2012X145N")
      (fields
        (field (name "DB_PART_NUMBER") "CAP000043686")
        (field (name "DB_VALUE") "22uF")
        (field (name "DB_TOLERANCE") "20%")
        (field (name "DB_VOLTAGE") "6.3V")
        (field (name "DB_MANUFACTURER_PART") "KEMET    C0805C226M9PAC")
        (field (name "DB_APPROVED_BY") "ISHIDDEN=T")
      )
      (libsource (lib "Database_Libs1") (part "C"))
    )
    (comp (ref "C144")
      (value "C")
      (footprint "SMD_0805_CAPC2012X145N")
      (fields
        (field (name "DB_PART_NUMBER") "CAP000043686")
        (field (name "DB_VALUE") "22uF")
        (field (name "DB_TOLERANCE") "20%")
        (field (name "DB_VOLTAGE") "6.3V")
        (field (name "DB_MANUFACTURER_PART") "KEMET    C0805C226M9PAC")
        (field (name "DB_APPROVED_BY") "ISHIDDEN=T")
      )
      (libsource (lib "Database_Libs1") (part "C"))
    )
    (comp (ref "C145")
      (value "C")
      (footprint "SMD_0805_CAPC2012X145N")
      (fields
        (field (name "DB_PART_NUMBER") "CAP000043686")
        (field (name "DB_VALUE") "22uF")
        (field (name "DB_TOLERANCE") "20%")
        (field (name "DB_VOLTAGE") "6.3V")
        (field (name "DB_MANUFACTURER_PART") "KEMET    C0805C226M9PAC")
        (field (name "DB_APPROVED_BY") "ISHIDDEN=T")
      )
      (libsource (lib "Database_Libs1") (part "C"))
    )
    (comp (ref "C146")
      (value "C")
      (footprint "SMD_0805_CAPC2012X145N")
      (fields
        (field (name "DB_PART_NUMBER") "CAP000043686")
        (field (name "DB_VALUE") "22uF")
        (field (name "DB_TOLERANCE") "20%")
        (field (name "DB_VOLTAGE") "6.3V")
        (field (name "DB_MANUFACTURER_PART") "KEMET    C0805C226M9PAC")
        (field (name "DB_APPROVED_BY") "ISHIDDEN=T")
      )
      (libsource (lib "Database_Libs1") (part "C"))
    )
    (comp (ref "C147")
      (value "C")
      (footprint "SMD_0805_CAPC2012X145N")
      (fields
        (field (name "DB_PART_NUMBER") "CAP000043686")
        (field (name "DB_VALUE") "22uF")
        (field (name "DB_TOLERANCE") "20%")
        (field (name "DB_VOLTAGE") "6.3V")
        (field (name "DB_MANUFACTURER_PART") "KEMET    C0805C226M9PAC")
        (field (name "DB_APPROVED_BY") "ISHIDDEN=T")
      )
      (libsource (lib "Database_Libs1") (part "C"))
    )
    (comp (ref "C148")
      (value "C")
      (footprint "SMD_0805_CAPC2012X145N")
      (fields
        (field (name "DB_PART_NUMBER") "CAP000043686")
        (field (name "DB_VALUE") "22uF")
        (field (name "DB_TOLERANCE") "20%")
        (field (name "DB_VOLTAGE") "6.3V")
        (field (name "DB_MANUFACTURER_PART") "KEMET    C0805C226M9PAC")
        (field (name "DB_APPROVED_BY") "ISHIDDEN=T")
      )
      (libsource (lib "Database_Libs1") (part "C"))
    )
    (comp (ref "C149")
      (value "C")
      (footprint "SMD_0805_CAPC2012X145N")
      (fields
        (field (name "DB_PART_NUMBER") "CAP000043686")
        (field (name "DB_VALUE") "22uF")
        (field (name "DB_TOLERANCE") "20%")
        (field (name "DB_VOLTAGE") "6.3V")
        (field (name "DB_MANUFACTURER_PART") "KEMET    C0805C226M9PAC")
        (field (name "DB_APPROVED_BY") "ISHIDDEN=T")
      )
      (libsource (lib "Database_Libs1") (part "C"))
    )
    (comp (ref "C150")
      (value "C")
      (footprint "SMD_0805_CAPC2012X145N")
      (fields
        (field (name "DB_PART_NUMBER") "CAP000043686")
        (field (name "DB_VALUE") "22uF")
        (field (name "DB_TOLERANCE") "20%")
        (field (name "DB_VOLTAGE") "6.3V")
        (field (name "DB_MANUFACTURER_PART") "KEMET    C0805C226M9PAC")
        (field (name "DB_APPROVED_BY") "ISHIDDEN=T")
      )
      (libsource (lib "Database_Libs1") (part "C"))
    )
    (comp (ref "C151")
      (value "C")
      (footprint "SMD_0805_CAPC2012X145N")
      (fields
        (field (name "DB_PART_NUMBER") "CAP000043686")
        (field (name "DB_VALUE") "22uF")
        (field (name "DB_TOLERANCE") "20%")
        (field (name "DB_VOLTAGE") "6.3V")
        (field (name "DB_MANUFACTURER_PART") "KEMET    C0805C226M9PAC")
        (field (name "DB_APPROVED_BY") "ISHIDDEN=T")
      )
      (libsource (lib "Database_Libs1") (part "C"))
    )
    (comp (ref "C152")
      (value "C")
      (footprint "SMD_0805_CAPC2012X145N")
      (fields
        (field (name "DB_PART_NUMBER") "CAP000043686")
        (field (name "DB_VALUE") "22uF")
        (field (name "DB_TOLERANCE") "20%")
        (field (name "DB_VOLTAGE") "6.3V")
        (field (name "DB_MANUFACTURER_PART") "KEMET    C0805C226M9PAC")
        (field (name "DB_APPROVED_BY") "ISHIDDEN=T")
      )
      (libsource (lib "Database_Libs1") (part "C"))
    )
    (comp (ref "C153")
      (value "C")
      (footprint "SMD_0805_CAPC2012X145N")
      (fields
        (field (name "DB_PART_NUMBER") "CAP000043686")
        (field (name "DB_VALUE") "22uF")
        (field (name "DB_TOLERANCE") "20%")
        (field (name "DB_VOLTAGE") "6.3V")
        (field (name "DB_MANUFACTURER_PART") "KEMET    C0805C226M9PAC")
        (field (name "DB_APPROVED_BY") "ISHIDDEN=T")
      )
      (libsource (lib "Database_Libs1") (part "C"))
    )
    (comp (ref "C154")
      (value "C")
      (footprint "SMD_0805_CAPC2012X145N")
      (fields
        (field (name "DB_PART_NUMBER") "CAP000043686")
        (field (name "DB_VALUE") "22uF")
        (field (name "DB_TOLERANCE") "20%")
        (field (name "DB_VOLTAGE") "6.3V")
        (field (name "DB_MANUFACTURER_PART") "KEMET    C0805C226M9PAC")
        (field (name "DB_APPROVED_BY") "ISHIDDEN=T")
      )
      (libsource (lib "Database_Libs1") (part "C"))
    )
    (comp (ref "C155")
      (value "C")
      (footprint "SMD_0805_CAPC2012X145N")
      (fields
        (field (name "DB_PART_NUMBER") "CAP000043686")
        (field (name "DB_VALUE") "22uF")
        (field (name "DB_TOLERANCE") "20%")
        (field (name "DB_VOLTAGE") "6.3V")
        (field (name "DB_MANUFACTURER_PART") "KEMET    C0805C226M9PAC")
        (field (name "DB_APPROVED_BY") "ISHIDDEN=T")
      )
      (libsource (lib "Database_Libs1") (part "C"))
    )
    (comp (ref "C156")
      (value "C")
      (footprint "SMD_1210_CAPC3225X279N")
      (fields
        (field (name "DB_PART_NUMBER") "CAP000047355")
        (field (name "DB_VALUE") "220uF")
        (field (name "DB_TOLERANCE") "20%")
        (field (name "DB_VOLTAGE") "6.3V")
        (field (name "DB_MANUFACTURER_PART") "SAMSUNG    CL32A227MQVNNNE")
        (field (name "DB_APPROVED_BY") "VSN")
      )
      (libsource (lib "Database_Libs1") (part "C"))
    )
    (comp (ref "C157")
      (value "C")
      (footprint "SMD_1210_CAPC3225X279N")
      (fields
        (field (name "DB_PART_NUMBER") "CAP000047355")
        (field (name "DB_VALUE") "220uF")
        (field (name "DB_TOLERANCE") "20%")
        (field (name "DB_VOLTAGE") "6.3V")
        (field (name "DB_MANUFACTURER_PART") "SAMSUNG    CL32A227MQVNNNE")
        (field (name "DB_APPROVED_BY") "VSN")
      )
      (libsource (lib "Database_Libs1") (part "C"))
    )
    (comp (ref "C158")
      (value "C")
      (footprint "SMD_1210_CAPC3225X279N")
      (fields
        (field (name "DB_PART_NUMBER") "CAP000047355")
        (field (name "DB_VALUE") "220uF")
        (field (name "DB_TOLERANCE") "20%")
        (field (name "DB_VOLTAGE") "6.3V")
        (field (name "DB_MANUFACTURER_PART") "SAMSUNG    CL32A227MQVNNNE")
        (field (name "DB_APPROVED_BY") "VSN")
      )
      (libsource (lib "Database_Libs1") (part "C"))
    )
    (comp (ref "C159")
      (value "C")
      (footprint "SMD_1210_CAPC3225X279N")
      (fields
        (field (name "DB_PART_NUMBER") "CAP000047355")
        (field (name "DB_VALUE") "220uF")
        (field (name "DB_TOLERANCE") "20%")
        (field (name "DB_VOLTAGE") "6.3V")
        (field (name "DB_MANUFACTURER_PART") "SAMSUNG    CL32A227MQVNNNE")
        (field (name "DB_APPROVED_BY") "VSN")
      )
      (libsource (lib "Database_Libs1") (part "C"))
    )
    (comp (ref "C160")
      (value "C")
      (footprint "SMD_1210_CAPC3225X279N")
      (fields
        (field (name "DB_PART_NUMBER") "CAP000047355")
        (field (name "DB_VALUE") "220uF")
        (field (name "DB_TOLERANCE") "20%")
        (field (name "DB_VOLTAGE") "6.3V")
        (field (name "DB_MANUFACTURER_PART") "SAMSUNG    CL32A227MQVNNNE")
        (field (name "DB_APPROVED_BY") "VSN")
      )
      (libsource (lib "Database_Libs1") (part "C"))
    )
    (comp (ref "C161")
      (value "C")
      (footprint "SMD_1210_CAPC3225X279N")
      (fields
        (field (name "DB_PART_NUMBER") "CAP000047355")
        (field (name "DB_VALUE") "220uF")
        (field (name "DB_TOLERANCE") "20%")
        (field (name "DB_VOLTAGE") "6.3V")
        (field (name "DB_MANUFACTURER_PART") "SAMSUNG    CL32A227MQVNNNE")
        (field (name "DB_APPROVED_BY") "VSN")
      )
      (libsource (lib "Database_Libs1") (part "C"))
    )
    (comp (ref "C162")
      (value "C")
      (footprint "SMD_1210_CAPC3225X279N")
      (fields
        (field (name "DB_PART_NUMBER") "CAP000047355")
        (field (name "DB_VALUE") "220uF")
        (field (name "DB_TOLERANCE") "20%")
        (field (name "DB_VOLTAGE") "6.3V")
        (field (name "DB_MANUFACTURER_PART") "SAMSUNG    CL32A227MQVNNNE")
        (field (name "DB_APPROVED_BY") "VSN")
      )
      (libsource (lib "Database_Libs1") (part "C"))
    )
    (comp (ref "C163")
      (value "C")
      (footprint "SMD_1210_CAPC3225X279N")
      (fields
        (field (name "DB_PART_NUMBER") "CAP000047355")
        (field (name "DB_VALUE") "220uF")
        (field (name "DB_TOLERANCE") "20%")
        (field (name "DB_VOLTAGE") "6.3V")
        (field (name "DB_MANUFACTURER_PART") "SAMSUNG    CL32A227MQVNNNE")
        (field (name "DB_APPROVED_BY") "VSN")
      )
      (libsource (lib "Database_Libs1") (part "C"))
    )
    (comp (ref "C164")
      (value "C")
      (footprint "SMD_1210_CAPC3225X279N")
      (fields
        (field (name "DB_PART_NUMBER") "CAP000047355")
        (field (name "DB_VALUE") "220uF")
        (field (name "DB_TOLERANCE") "20%")
        (field (name "DB_VOLTAGE") "6.3V")
        (field (name "DB_MANUFACTURER_PART") "SAMSUNG    CL32A227MQVNNNE")
        (field (name "DB_APPROVED_BY") "VSN")
      )
      (libsource (lib "Database_Libs1") (part "C"))
    )
    (comp (ref "C165")
      (value "C")
      (footprint "SMD_1210_CAPC3225X279N")
      (fields
        (field (name "DB_PART_NUMBER") "CAP000047355")
        (field (name "DB_VALUE") "220uF")
        (field (name "DB_TOLERANCE") "20%")
        (field (name "DB_VOLTAGE") "6.3V")
        (field (name "DB_MANUFACTURER_PART") "SAMSUNG    CL32A227MQVNNNE")
        (field (name "DB_APPROVED_BY") "VSN")
      )
      (libsource (lib "Database_Libs1") (part "C"))
    )
    (comp (ref "C166")
      (value "C")
      (footprint "SMD_0805_CAPC2012X145N")
      (fields
        (field (name "DB_PART_NUMBER") "CAP000043686")
        (field (name "DB_VALUE") "22uF")
        (field (name "DB_TOLERANCE") "20%")
        (field (name "DB_VOLTAGE") "6.3V")
        (field (name "DB_MANUFACTURER_PART") "KEMET    C0805C226M9PAC")
        (field (name "DB_APPROVED_BY") "ISHIDDEN=T")
      )
      (libsource (lib "Database_Libs1") (part "C"))
    )
    (comp (ref "C167")
      (value "C")
      (footprint "SMD_0805_CAPC2012X145N")
      (fields
        (field (name "DB_PART_NUMBER") "CAP000043686")
        (field (name "DB_VALUE") "22uF")
        (field (name "DB_TOLERANCE") "20%")
        (field (name "DB_VOLTAGE") "6.3V")
        (field (name "DB_MANUFACTURER_PART") "KEMET    C0805C226M9PAC")
        (field (name "DB_APPROVED_BY") "ISHIDDEN=T")
      )
      (libsource (lib "Database_Libs1") (part "C"))
    )
    (comp (ref "C169")
      (value "C")
      (footprint "SMD_0805_CAPC2012X145N")
      (fields
        (field (name "DB_PART_NUMBER") "CAP000043686")
        (field (name "DB_VALUE") "22uF")
        (field (name "DB_TOLERANCE") "20%")
        (field (name "DB_VOLTAGE") "6.3V")
        (field (name "DB_MANUFACTURER_PART") "KEMET    C0805C226M9PAC")
        (field (name "DB_APPROVED_BY") "ISHIDDEN=T")
      )
      (libsource (lib "Database_Libs1") (part "C"))
    )
    (comp (ref "C170")
      (value "C")
      (footprint "SMD_0805_CAPC2012X145N")
      (fields
        (field (name "DB_PART_NUMBER") "CAP000043686")
        (field (name "DB_VALUE") "22uF")
        (field (name "DB_TOLERANCE") "20%")
        (field (name "DB_VOLTAGE") "6.3V")
        (field (name "DB_MANUFACTURER_PART") "KEMET    C0805C226M9PAC")
        (field (name "DB_APPROVED_BY") "ISHIDDEN=T")
      )
      (libsource (lib "Database_Libs1") (part "C"))
    )
    (comp (ref "C171")
      (value "C")
      (footprint "SMD_0805_CAPC2012X145N")
      (fields
        (field (name "DB_PART_NUMBER") "CAP000043686")
        (field (name "DB_VALUE") "22uF")
        (field (name "DB_TOLERANCE") "20%")
        (field (name "DB_VOLTAGE") "6.3V")
        (field (name "DB_MANUFACTURER_PART") "KEMET    C0805C226M9PAC")
        (field (name "DB_APPROVED_BY") "ISHIDDEN=T")
      )
      (libsource (lib "Database_Libs1") (part "C"))
    )
    (comp (ref "C172")
      (value "C")
      (footprint "SMD_0805_CAPC2012X145N")
      (fields
        (field (name "DB_PART_NUMBER") "CAP000043686")
        (field (name "DB_VALUE") "22uF")
        (field (name "DB_TOLERANCE") "20%")
        (field (name "DB_VOLTAGE") "6.3V")
        (field (name "DB_MANUFACTURER_PART") "KEMET    C0805C226M9PAC")
        (field (name "DB_APPROVED_BY") "ISHIDDEN=T")
      )
      (libsource (lib "Database_Libs1") (part "C"))
    )
    (comp (ref "C173")
      (value "C")
      (footprint "SMD_0805_CAPC2012X145N")
      (fields
        (field (name "DB_PART_NUMBER") "CAP000043686")
        (field (name "DB_VALUE") "22uF")
        (field (name "DB_TOLERANCE") "20%")
        (field (name "DB_VOLTAGE") "6.3V")
        (field (name "DB_MANUFACTURER_PART") "KEMET    C0805C226M9PAC")
        (field (name "DB_APPROVED_BY") "ISHIDDEN=T")
      )
      (libsource (lib "Database_Libs1") (part "C"))
    )
    (comp (ref "C174")
      (value "C")
      (footprint "SMD_0805_CAPC2012X145N")
      (fields
        (field (name "DB_PART_NUMBER") "CAP000043686")
        (field (name "DB_VALUE") "22uF")
        (field (name "DB_TOLERANCE") "20%")
        (field (name "DB_VOLTAGE") "6.3V")
        (field (name "DB_MANUFACTURER_PART") "KEMET    C0805C226M9PAC")
        (field (name "DB_APPROVED_BY") "ISHIDDEN=T")
      )
      (libsource (lib "Database_Libs1") (part "C"))
    )
    (comp (ref "C175")
      (value "C")
      (footprint "SMD_0805_CAPC2012X145N")
      (fields
        (field (name "DB_PART_NUMBER") "CAP000043686")
        (field (name "DB_VALUE") "22uF")
        (field (name "DB_TOLERANCE") "20%")
        (field (name "DB_VOLTAGE") "6.3V")
        (field (name "DB_MANUFACTURER_PART") "KEMET    C0805C226M9PAC")
        (field (name "DB_APPROVED_BY") "ISHIDDEN=T")
      )
      (libsource (lib "Database_Libs1") (part "C"))
    )
    (comp (ref "C176")
      (value "C")
      (footprint "SMD_0805_CAPC2012X145N")
      (fields
        (field (name "DB_PART_NUMBER") "CAP000043686")
        (field (name "DB_VALUE") "22uF")
        (field (name "DB_TOLERANCE") "20%")
        (field (name "DB_VOLTAGE") "6.3V")
        (field (name "DB_MANUFACTURER_PART") "KEMET    C0805C226M9PAC")
        (field (name "DB_APPROVED_BY") "ISHIDDEN=T")
      )
      (libsource (lib "Database_Libs1") (part "C"))
    )
    (comp (ref "C177")
      (value "C")
      (footprint "SMD_0805_CAPC2012X145N")
      (fields
        (field (name "DB_PART_NUMBER") "CAP000043686")
        (field (name "DB_VALUE") "22uF")
        (field (name "DB_TOLERANCE") "20%")
        (field (name "DB_VOLTAGE") "6.3V")
        (field (name "DB_MANUFACTURER_PART") "KEMET    C0805C226M9PAC")
        (field (name "DB_APPROVED_BY") "ISHIDDEN=T")
      )
      (libsource (lib "Database_Libs1") (part "C"))
    )
    (comp (ref "C178")
      (value "C")
      (footprint "SMD_0805_CAPC2012X145N")
      (fields
        (field (name "DB_PART_NUMBER") "CAP000043686")
        (field (name "DB_VALUE") "22uF")
        (field (name "DB_TOLERANCE") "20%")
        (field (name "DB_VOLTAGE") "6.3V")
        (field (name "DB_MANUFACTURER_PART") "KEMET    C0805C226M9PAC")
        (field (name "DB_APPROVED_BY") "ISHIDDEN=T")
      )
      (libsource (lib "Database_Libs1") (part "C"))
    )
    (comp (ref "C179")
      (value "C")
      (footprint "SMD_0805_CAPC2012X145N")
      (fields
        (field (name "DB_PART_NUMBER") "CAP000043686")
        (field (name "DB_VALUE") "22uF")
        (field (name "DB_TOLERANCE") "20%")
        (field (name "DB_VOLTAGE") "6.3V")
        (field (name "DB_MANUFACTURER_PART") "KEMET    C0805C226M9PAC")
        (field (name "DB_APPROVED_BY") "ISHIDDEN=T")
      )
      (libsource (lib "Database_Libs1") (part "C"))
    )
    (comp (ref "C180")
      (value "C")
      (footprint "SMD_0805_CAPC2012X145N")
      (fields
        (field (name "DB_PART_NUMBER") "CAP000043686")
        (field (name "DB_VALUE") "22uF")
        (field (name "DB_TOLERANCE") "20%")
        (field (name "DB_VOLTAGE") "6.3V")
        (field (name "DB_MANUFACTURER_PART") "KEMET    C0805C226M9PAC")
        (field (name "DB_APPROVED_BY") "ISHIDDEN=T")
      )
      (libsource (lib "Database_Libs1") (part "C"))
    )
    (comp (ref "C197")
      (value "C")
      (footprint "SMD_1210_CAPC3225X279N")
      (fields
        (field (name "DB_PART_NUMBER") "CAP000047355")
        (field (name "DB_VALUE") "220uF")
        (field (name "DB_TOLERANCE") "20%")
        (field (name "DB_VOLTAGE") "6.3V")
        (field (name "DB_MANUFACTURER_PART") "SAMSUNG    CL32A227MQVNNNE")
        (field (name "DB_APPROVED_BY") "VSN")
      )
      (libsource (lib "Database_Libs1") (part "C"))
    )
    (comp (ref "C198")
      (value "C")
      (footprint "SMD_1210_CAPC3225X279N")
      (fields
        (field (name "DB_PART_NUMBER") "CAP000047355")
        (field (name "DB_VALUE") "220uF")
        (field (name "DB_TOLERANCE") "20%")
        (field (name "DB_VOLTAGE") "6.3V")
        (field (name "DB_MANUFACTURER_PART") "SAMSUNG    CL32A227MQVNNNE")
        (field (name "DB_APPROVED_BY") "VSN")
      )
      (libsource (lib "Database_Libs1") (part "C"))
    )
    (comp (ref "C199")
      (value "C")
      (footprint "SMD_1210_CAPC3225X279N")
      (fields
        (field (name "DB_PART_NUMBER") "CAP000047355")
        (field (name "DB_VALUE") "220uF")
        (field (name "DB_TOLERANCE") "20%")
        (field (name "DB_VOLTAGE") "6.3V")
        (field (name "DB_MANUFACTURER_PART") "SAMSUNG    CL32A227MQVNNNE")
        (field (name "DB_APPROVED_BY") "VSN")
      )
      (libsource (lib "Database_Libs1") (part "C"))
    )
    (comp (ref "C200")
      (value "C")
      (footprint "SMD_1210_CAPC3225X279N")
      (fields
        (field (name "DB_PART_NUMBER") "CAP000047355")
        (field (name "DB_VALUE") "220uF")
        (field (name "DB_TOLERANCE") "20%")
        (field (name "DB_VOLTAGE") "6.3V")
        (field (name "DB_MANUFACTURER_PART") "SAMSUNG    CL32A227MQVNNNE")
        (field (name "DB_APPROVED_BY") "VSN")
      )
      (libsource (lib "Database_Libs1") (part "C"))
    )
    (comp (ref "C201")
      (value "C")
      (footprint "SMD_1210_CAPC3225X279N")
      (fields
        (field (name "DB_PART_NUMBER") "CAP000047355")
        (field (name "DB_VALUE") "220uF")
        (field (name "DB_TOLERANCE") "20%")
        (field (name "DB_VOLTAGE") "6.3V")
        (field (name "DB_MANUFACTURER_PART") "SAMSUNG    CL32A227MQVNNNE")
        (field (name "DB_APPROVED_BY") "VSN")
      )
      (libsource (lib "Database_Libs1") (part "C"))
    )
    (comp (ref "C202")
      (value "C")
      (footprint "SMD_1210_CAPC3225X279N")
      (fields
        (field (name "DB_PART_NUMBER") "CAP000047355")
        (field (name "DB_VALUE") "220uF")
        (field (name "DB_TOLERANCE") "20%")
        (field (name "DB_VOLTAGE") "6.3V")
        (field (name "DB_MANUFACTURER_PART") "SAMSUNG    CL32A227MQVNNNE")
        (field (name "DB_APPROVED_BY") "VSN")
      )
      (libsource (lib "Database_Libs1") (part "C"))
    )
    (comp (ref "C203")
      (value "C")
      (footprint "SMD_1210_CAPC3225X279N")
      (fields
        (field (name "DB_PART_NUMBER") "CAP000047355")
        (field (name "DB_VALUE") "220uF")
        (field (name "DB_TOLERANCE") "20%")
        (field (name "DB_VOLTAGE") "6.3V")
        (field (name "DB_MANUFACTURER_PART") "SAMSUNG    CL32A227MQVNNNE")
        (field (name "DB_APPROVED_BY") "VSN")
      )
      (libsource (lib "Database_Libs1") (part "C"))
    )
    (comp (ref "C204")
      (value "C")
      (footprint "SMD_1210_CAPC3225X279N")
      (fields
        (field (name "DB_PART_NUMBER") "CAP000047355")
        (field (name "DB_VALUE") "220uF")
        (field (name "DB_TOLERANCE") "20%")
        (field (name "DB_VOLTAGE") "6.3V")
        (field (name "DB_MANUFACTURER_PART") "SAMSUNG    CL32A227MQVNNNE")
        (field (name "DB_APPROVED_BY") "VSN")
      )
      (libsource (lib "Database_Libs1") (part "C"))
    )
    (comp (ref "C205")
      (value "C")
      (footprint "SMD_1210_CAPC3225X279N")
      (fields
        (field (name "DB_PART_NUMBER") "CAP000047355")
        (field (name "DB_VALUE") "220uF")
        (field (name "DB_TOLERANCE") "20%")
        (field (name "DB_VOLTAGE") "6.3V")
        (field (name "DB_MANUFACTURER_PART") "SAMSUNG    CL32A227MQVNNNE")
        (field (name "DB_APPROVED_BY") "VSN")
      )
      (libsource (lib "Database_Libs1") (part "C"))
    )
    (comp (ref "C206")
      (value "C")
      (footprint "SMD_1210_CAPC3225X279N")
      (fields
        (field (name "DB_PART_NUMBER") "CAP000047355")
        (field (name "DB_VALUE") "220uF")
        (field (name "DB_TOLERANCE") "20%")
        (field (name "DB_VOLTAGE") "6.3V")
        (field (name "DB_MANUFACTURER_PART") "SAMSUNG    CL32A227MQVNNNE")
        (field (name "DB_APPROVED_BY") "VSN")
      )
      (libsource (lib "Database_Libs1") (part "C"))
    )
    (comp (ref "C207")
      (value "C")
      (footprint "SMD_1210_CAPC3225X279N")
      (fields
        (field (name "DB_PART_NUMBER") "CAP000047355")
        (field (name "DB_VALUE") "220uF")
        (field (name "DB_TOLERANCE") "20%")
        (field (name "DB_VOLTAGE") "6.3V")
        (field (name "DB_MANUFACTURER_PART") "SAMSUNG    CL32A227MQVNNNE")
        (field (name "DB_APPROVED_BY") "VSN")
      )
      (libsource (lib "Database_Libs1") (part "C"))
    )
    (comp (ref "C208")
      (value "C")
      (footprint "SMD_1210_CAPC3225X279N")
      (fields
        (field (name "DB_PART_NUMBER") "CAP000047355")
        (field (name "DB_VALUE") "220uF")
        (field (name "DB_TOLERANCE") "20%")
        (field (name "DB_VOLTAGE") "6.3V")
        (field (name "DB_MANUFACTURER_PART") "SAMSUNG    CL32A227MQVNNNE")
        (field (name "DB_APPROVED_BY") "VSN")
      )
      (libsource (lib "Database_Libs1") (part "C"))
    )
    (comp (ref "C209")
      (value "C")
      (footprint "SMD_1210_CAPC3225X279N")
      (fields
        (field (name "DB_PART_NUMBER") "CAP000047355")
        (field (name "DB_VALUE") "220uF")
        (field (name "DB_TOLERANCE") "20%")
        (field (name "DB_VOLTAGE") "6.3V")
        (field (name "DB_MANUFACTURER_PART") "SAMSUNG    CL32A227MQVNNNE")
        (field (name "DB_APPROVED_BY") "VSN")
      )
      (libsource (lib "Database_Libs1") (part "C"))
    )
    (comp (ref "C210")
      (value "C")
      (footprint "SMD_1210_CAPC3225X279N")
      (fields
        (field (name "DB_PART_NUMBER") "CAP000047355")
        (field (name "DB_VALUE") "220uF")
        (field (name "DB_TOLERANCE") "20%")
        (field (name "DB_VOLTAGE") "6.3V")
        (field (name "DB_MANUFACTURER_PART") "SAMSUNG    CL32A227MQVNNNE")
        (field (name "DB_APPROVED_BY") "VSN")
      )
      (libsource (lib "Database_Libs1") (part "C"))
    )
    (comp (ref "C211")
      (value "C")
      (footprint "SMD_1210_CAPC3225X279N")
      (fields
        (field (name "DB_PART_NUMBER") "CAP000047355")
        (field (name "DB_VALUE") "220uF")
        (field (name "DB_TOLERANCE") "20%")
        (field (name "DB_VOLTAGE") "6.3V")
        (field (name "DB_MANUFACTURER_PART") "SAMSUNG    CL32A227MQVNNNE")
        (field (name "DB_APPROVED_BY") "VSN")
      )
      (libsource (lib "Database_Libs1") (part "C"))
    )
    (comp (ref "C212")
      (value "C")
      (footprint "SMD_1210_CAPC3225X279N")
      (fields
        (field (name "DB_PART_NUMBER") "CAP000047355")
        (field (name "DB_VALUE") "220uF")
        (field (name "DB_TOLERANCE") "20%")
        (field (name "DB_VOLTAGE") "6.3V")
        (field (name "DB_MANUFACTURER_PART") "SAMSUNG    CL32A227MQVNNNE")
        (field (name "DB_APPROVED_BY") "VSN")
      )
      (libsource (lib "Database_Libs1") (part "C"))
    )
    (comp (ref "C213")
      (value "C")
      (footprint "SMD_1210_CAPC3225X279N")
      (fields
        (field (name "DB_PART_NUMBER") "CAP000047355")
        (field (name "DB_VALUE") "220uF")
        (field (name "DB_TOLERANCE") "20%")
        (field (name "DB_VOLTAGE") "6.3V")
        (field (name "DB_MANUFACTURER_PART") "SAMSUNG    CL32A227MQVNNNE")
        (field (name "DB_APPROVED_BY") "VSN")
      )
      (libsource (lib "Database_Libs1") (part "C"))
    )
    (comp (ref "C214")
      (value "C")
      (footprint "SMD_1210_CAPC3225X279N")
      (fields
        (field (name "DB_PART_NUMBER") "CAP000047355")
        (field (name "DB_VALUE") "220uF")
        (field (name "DB_TOLERANCE") "20%")
        (field (name "DB_VOLTAGE") "6.3V")
        (field (name "DB_MANUFACTURER_PART") "SAMSUNG    CL32A227MQVNNNE")
        (field (name "DB_APPROVED_BY") "VSN")
      )
      (libsource (lib "Database_Libs1") (part "C"))
    )
    (comp (ref "C239")
      (value "C")
      (footprint "SMD_1210_CAPC3225X279N")
      (fields
        (field (name "DB_PART_NUMBER") "CAP000047355")
        (field (name "DB_VALUE") "220uF")
        (field (name "DB_TOLERANCE") "20%")
        (field (name "DB_VOLTAGE") "6.3V")
        (field (name "DB_MANUFACTURER_PART") "SAMSUNG    CL32A227MQVNNNE")
        (field (name "DB_APPROVED_BY") "VSN")
      )
      (libsource (lib "Database_Libs1") (part "C"))
    )
    (comp (ref "C289")
      (value "C")
      (footprint "SMD_0603_CAPC1608X95N")
      (fields
        (field (name "DB_PART_NUMBER") "CAP000027236")
        (field (name "DB_VALUE") "100nF")
        (field (name "DB_TOLERANCE") "20%")
        (field (name "DB_VOLTAGE") "16V")
        (field (name "DB_MANUFACTURER_PART") "KEMET    C0603C104M4RAC")
        (field (name "DB_APPROVED_BY") "ISHIDDEN=T")
      )
      (libsource (lib "Database_Libs1") (part "C"))
    )
    (comp (ref "C291")
      (value "C")
      (footprint "SMD_0603_CAPC1608X95N")
      (fields
        (field (name "DB_PART_NUMBER") "CAP000027236")
        (field (name "DB_VALUE") "100nF")
        (field (name "DB_TOLERANCE") "20%")
        (field (name "DB_VOLTAGE") "16V")
        (field (name "DB_MANUFACTURER_PART") "KEMET    C0603C104M4RAC")
        (field (name "DB_APPROVED_BY") "ISHIDDEN=T")
      )
      (libsource (lib "Database_Libs1") (part "C"))
    )
    (comp (ref "C293")
      (value "C")
      (footprint "SMD_0603_CAPC1608X95N")
      (fields
        (field (name "DB_PART_NUMBER") "CAP000027236")
        (field (name "DB_VALUE") "100nF")
        (field (name "DB_TOLERANCE") "20%")
        (field (name "DB_VOLTAGE") "16V")
        (field (name "DB_MANUFACTURER_PART") "KEMET    C0603C104M4RAC")
        (field (name "DB_APPROVED_BY") "ISHIDDEN=T")
      )
      (libsource (lib "Database_Libs1") (part "C"))
    )
    (comp (ref "C294")
      (value "C")
      (footprint "SMD_0603_CAPC1608X95N")
      (fields
        (field (name "DB_PART_NUMBER") "CAP000027236")
        (field (name "DB_VALUE") "100nF")
        (field (name "DB_TOLERANCE") "20%")
        (field (name "DB_VOLTAGE") "16V")
        (field (name "DB_MANUFACTURER_PART") "KEMET    C0603C104M4RAC")
        (field (name "DB_APPROVED_BY") "ISHIDDEN=T")
      )
      (libsource (lib "Database_Libs1") (part "C"))
    )
    (comp (ref "C303")
      (value "C")
      (footprint "SMD_0603_CAPC1608X95N")
      (fields
        (field (name "DB_PART_NUMBER") "CAP000027236")
        (field (name "DB_VALUE") "100nF")
        (field (name "DB_TOLERANCE") "20%")
        (field (name "DB_VOLTAGE") "16V")
        (field (name "DB_MANUFACTURER_PART") "KEMET    C0603C104M4RAC")
        (field (name "DB_APPROVED_BY") "ISHIDDEN=T")
      )
      (libsource (lib "Database_Libs1") (part "C"))
    )
    (comp (ref "C304")
      (value "C")
      (footprint "SMD_0603_CAPC1608X95N")
      (fields
        (field (name "DB_PART_NUMBER") "CAP000027236")
        (field (name "DB_VALUE") "100nF")
        (field (name "DB_TOLERANCE") "20%")
        (field (name "DB_VOLTAGE") "16V")
        (field (name "DB_MANUFACTURER_PART") "KEMET    C0603C104M4RAC")
        (field (name "DB_APPROVED_BY") "ISHIDDEN=T")
      )
      (libsource (lib "Database_Libs1") (part "C"))
    )
    (comp (ref "C305")
      (value "C")
      (footprint "SMD_0603_CAPC1608X95N")
      (fields
        (field (name "DB_PART_NUMBER") "CAP000027236")
        (field (name "DB_VALUE") "100nF")
        (field (name "DB_TOLERANCE") "20%")
        (field (name "DB_VOLTAGE") "16V")
        (field (name "DB_MANUFACTURER_PART") "KEMET    C0603C104M4RAC")
        (field (name "DB_APPROVED_BY") "ISHIDDEN=T")
      )
      (libsource (lib "Database_Libs1") (part "C"))
    )
    (comp (ref "C306")
      (value "C")
      (footprint "SMD_0603_CAPC1608X95N")
      (fields
        (field (name "DB_PART_NUMBER") "CAP000027236")
        (field (name "DB_VALUE") "100nF")
        (field (name "DB_TOLERANCE") "20%")
        (field (name "DB_VOLTAGE") "16V")
        (field (name "DB_MANUFACTURER_PART") "KEMET    C0603C104M4RAC")
        (field (name "DB_APPROVED_BY") "ISHIDDEN=T")
      )
      (libsource (lib "Database_Libs1") (part "C"))
    )
    (comp (ref "C307")
      (value "C")
      (footprint "SMD_0603_CAPC1608X95N")
      (fields
        (field (name "DB_PART_NUMBER") "CAP000027236")
        (field (name "DB_VALUE") "100nF")
        (field (name "DB_TOLERANCE") "20%")
        (field (name "DB_VOLTAGE") "16V")
        (field (name "DB_MANUFACTURER_PART") "KEMET    C0603C104M4RAC")
        (field (name "DB_APPROVED_BY") "ISHIDDEN=T")
      )
      (libsource (lib "Database_Libs1") (part "C"))
    )
    (comp (ref "C309")
      (value "C")
      (footprint "SMD_0603_CAPC1608X95N")
      (fields
        (field (name "DB_PART_NUMBER") "CAP000027236")
        (field (name "DB_VALUE") "100nF")
        (field (name "DB_TOLERANCE") "20%")
        (field (name "DB_VOLTAGE") "16V")
        (field (name "DB_MANUFACTURER_PART") "KEMET    C0603C104M4RAC")
        (field (name "DB_APPROVED_BY") "ISHIDDEN=T")
      )
      (libsource (lib "Database_Libs1") (part "C"))
    )
    (comp (ref "C315")
      (value "C")
      (footprint "SMD_0603_CAPC1608X95N")
      (fields
        (field (name "DB_PART_NUMBER") "CAP000027236")
        (field (name "DB_VALUE") "100nF")
        (field (name "DB_TOLERANCE") "20%")
        (field (name "DB_VOLTAGE") "16V")
        (field (name "DB_MANUFACTURER_PART") "KEMET    C0603C104M4RAC")
        (field (name "DB_APPROVED_BY") "ISHIDDEN=T")
      )
      (libsource (lib "Database_Libs1") (part "C"))
    )
    (comp (ref "C322")
      (value "C")
      (footprint "SMD_0603_CAPC1608X95N")
      (fields
        (field (name "DB_PART_NUMBER") "CAP000027236")
        (field (name "DB_VALUE") "100nF")
        (field (name "DB_TOLERANCE") "20%")
        (field (name "DB_VOLTAGE") "16V")
        (field (name "DB_MANUFACTURER_PART") "KEMET    C0603C104M4RAC")
        (field (name "DB_APPROVED_BY") "ISHIDDEN=T")
      )
      (libsource (lib "Database_Libs1") (part "C"))
    )
    (comp (ref "C594")
      (value "C")
      (footprint "SMD_0603_CAPC1608X95N")
      (fields
        (field (name "DB_PART_NUMBER") "CAP000027236")
        (field (name "DB_VALUE") "100nF")
        (field (name "DB_TOLERANCE") "20%")
        (field (name "DB_VOLTAGE") "16V")
        (field (name "DB_MANUFACTURER_PART") "KEMET    C0603C104M4RAC")
        (field (name "DB_APPROVED_BY") "ISHIDDEN=T")
      )
      (libsource (lib "Database_Libs1") (part "C"))
    )
    (comp (ref "C595")
      (value "C")
      (footprint "SMD_0603_CAPC1608X95N")
      (fields
        (field (name "DB_PART_NUMBER") "CAP000027236")
        (field (name "DB_VALUE") "100nF")
        (field (name "DB_TOLERANCE") "20%")
        (field (name "DB_VOLTAGE") "16V")
        (field (name "DB_MANUFACTURER_PART") "KEMET    C0603C104M4RAC")
        (field (name "DB_APPROVED_BY") "ISHIDDEN=T")
      )
      (libsource (lib "Database_Libs1") (part "C"))
    )
    (comp (ref "C597")
      (value "C")
      (footprint "SMD_0603_CAPC1608X95N")
      (fields
        (field (name "DB_PART_NUMBER") "CAP000027236")
        (field (name "DB_VALUE") "100nF")
        (field (name "DB_TOLERANCE") "20%")
        (field (name "DB_VOLTAGE") "16V")
        (field (name "DB_MANUFACTURER_PART") "KEMET    C0603C104M4RAC")
        (field (name "DB_APPROVED_BY") "ISHIDDEN=T")
      )
      (libsource (lib "Database_Libs1") (part "C"))
    )
    (comp (ref "C601")
      (value "C")
      (footprint "SMD_0603_CAPC1608X95N")
      (fields
        (field (name "DB_PART_NUMBER") "CAP000027236")
        (field (name "DB_VALUE") "100nF")
        (field (name "DB_TOLERANCE") "20%")
        (field (name "DB_VOLTAGE") "16V")
        (field (name "DB_MANUFACTURER_PART") "KEMET    C0603C104M4RAC")
        (field (name "DB_APPROVED_BY") "ISHIDDEN=T")
      )
      (libsource (lib "Database_Libs1") (part "C"))
    )
    (comp (ref "C604")
      (value "C")
      (footprint "SMD_0603_CAPC1608X95N")
      (fields
        (field (name "DB_PART_NUMBER") "CAP000027236")
        (field (name "DB_VALUE") "100nF")
        (field (name "DB_TOLERANCE") "20%")
        (field (name "DB_VOLTAGE") "16V")
        (field (name "DB_MANUFACTURER_PART") "KEMET    C0603C104M4RAC")
        (field (name "DB_APPROVED_BY") "ISHIDDEN=T")
      )
      (libsource (lib "Database_Libs1") (part "C"))
    )
    (comp (ref "C609")
      (value "C")
      (footprint "SMD_0603_CAPC1608X95N")
      (fields
        (field (name "DB_PART_NUMBER") "CAP000027236")
        (field (name "DB_VALUE") "100nF")
        (field (name "DB_TOLERANCE") "20%")
        (field (name "DB_VOLTAGE") "16V")
        (field (name "DB_MANUFACTURER_PART") "KEMET    C0603C104M4RAC")
        (field (name "DB_APPROVED_BY") "ISHIDDEN=T")
      )
      (libsource (lib "Database_Libs1") (part "C"))
    )
    (comp (ref "C610")
      (value "C")
      (footprint "SMD_0603_CAPC1608X95N")
      (fields
        (field (name "DB_PART_NUMBER") "CAP000027236")
        (field (name "DB_VALUE") "100nF")
        (field (name "DB_TOLERANCE") "20%")
        (field (name "DB_VOLTAGE") "16V")
        (field (name "DB_MANUFACTURER_PART") "KEMET    C0603C104M4RAC")
        (field (name "DB_APPROVED_BY") "ISHIDDEN=T")
      )
      (libsource (lib "Database_Libs1") (part "C"))
    )
    (comp (ref "C616")
      (value "C")
      (footprint "SMD_0603_CAPC1608X95N")
      (fields
        (field (name "DB_PART_NUMBER") "CAP000027236")
        (field (name "DB_VALUE") "100nF")
        (field (name "DB_TOLERANCE") "20%")
        (field (name "DB_VOLTAGE") "16V")
        (field (name "DB_MANUFACTURER_PART") "KEMET    C0603C104M4RAC")
        (field (name "DB_APPROVED_BY") "ISHIDDEN=T")
      )
      (libsource (lib "Database_Libs1") (part "C"))
    )
    (comp (ref "D5")
      (value "Red SML210VT ROHM")
      (footprint "SMD_0805_LED2012X100N")
      (fields
        (field (name "DB_PART_NUMBER") "OPT000000095")
        (field (name "DB_MANUFACTURER_PART") "KINGBRIGHT       KP-2012EC")
        (field (name "DB_VALUE") "KP-2012EC")
        (field (name "DB_APPROVED_BY") "VSN")
      )
      (libsource (lib "Database_Libs1") (part "LED"))
    )
    (comp (ref "D7")
      (value "Green  SML210MT ROHM")
      (footprint "SMD_0805_LED2012X100N")
      (fields
        (field (name "DB_PART_NUMBER") "OPT000000096")
        (field (name "DB_MANUFACTURER_PART") "KINGBRIGHT       KP-2012CGCK")
        (field (name "DB_VALUE") "KP-2012CGCK")
        (field (name "DB_APPROVED_BY") "VSN")
      )
      (libsource (lib "Database_Libs1") (part "LED"))
    )
    (comp (ref "D9")
      (value "Yellow SML210YT ROHM")
      (footprint "SMD_0805_LED2012X100N")
      (fields
        (field (name "DB_PART_NUMBER") "OPT000000092")
        (field (name "DB_MANUFACTURER_PART") "EVERLIGHT       17-21-Y2C-A0L1M2V0B-3T-AM")
        (field (name "DB_VALUE") "17-21-Y2C-A0L1M2V0B-3T-AM")
        (field (name "DB_APPROVED_BY") "VSN")
      )
      (libsource (lib "Database_Libs1") (part "LED"))
    )
    (comp (ref "D12")
      (value "Red SML210VT ROHM")
      (footprint "SMD_0805_LED2012X100N")
      (fields
        (field (name "DB_PART_NUMBER") "OPT000000095")
        (field (name "DB_MANUFACTURER_PART") "KINGBRIGHT       KP-2012EC")
        (field (name "DB_VALUE") "KP-2012EC")
        (field (name "DB_APPROVED_BY") "VSN")
      )
      (libsource (lib "Database_Libs1") (part "LED"))
    )
    (comp (ref "D13")
      (value "Green  SML210MT ROHM")
      (footprint "SMD_0805_LED2012X100N")
      (fields
        (field (name "DB_PART_NUMBER") "OPT000000096")
        (field (name "DB_MANUFACTURER_PART") "KINGBRIGHT       KP-2012CGCK")
        (field (name "DB_VALUE") "KP-2012CGCK")
        (field (name "DB_APPROVED_BY") "VSN")
      )
      (libsource (lib "Database_Libs1") (part "LED"))
    )
    (comp (ref "D16")
      (value "Yellow SML210YT ROHM")
      (footprint "SMD_0805_LED2012X100N")
      (fields
        (field (name "DB_PART_NUMBER") "OPT000000092")
        (field (name "DB_MANUFACTURER_PART") "EVERLIGHT       17-21-Y2C-A0L1M2V0B-3T-AM")
        (field (name "DB_VALUE") "17-21-Y2C-A0L1M2V0B-3T-AM")
        (field (name "DB_APPROVED_BY") "VSN")
      )
      (libsource (lib "Database_Libs1") (part "LED"))
    )
    (comp (ref "D17")
      (value "Orange  SML210DT ROHM")
      (footprint "SMD_0805_LED2012X100N")
      (fields
        (field (name "DB_PART_NUMBER") "OPT000000096")
        (field (name "DB_MANUFACTURER_PART") "KINGBRIGHT       KP-2012CGCK")
        (field (name "DB_APPROVED_BY") "VSN")
      )
      (libsource (lib "altium-import") (part "root_0_LED_Orange_"))
    )
    (comp (ref "D20")
      (value "Red SML210VT ROHM")
      (footprint "SMD_0805_LED2012X100N")
      (fields
        (field (name "DB_PART_NUMBER") "OPT000000095")
        (field (name "DB_MANUFACTURER_PART") "KINGBRIGHT       KP-2012EC")
        (field (name "DB_VALUE") "KP-2012EC")
        (field (name "DB_APPROVED_BY") "VSN")
      )
      (libsource (lib "Database_Libs1") (part "LED"))
    )
    (comp (ref "D21")
      (value "Red SML210VT ROHM")
      (footprint "SMD_0805_LED2012X100N")
      (fields
        (field (name "DB_PART_NUMBER") "OPT000000095")
        (field (name "DB_MANUFACTURER_PART") "KINGBRIGHT       KP-2012EC")
        (field (name "DB_VALUE") "KP-2012EC")
        (field (name "DB_APPROVED_BY") "VSN")
      )
      (libsource (lib "Database_Libs1") (part "LED"))
    )
    (comp (ref "D24")
      (value "Green  SML210MT ROHM")
      (footprint "SMD_0805_LED2012X100N")
      (fields
        (field (name "DB_PART_NUMBER") "OPT000000096")
        (field (name "DB_MANUFACTURER_PART") "KINGBRIGHT       KP-2012CGCK")
        (field (name "DB_VALUE") "KP-2012CGCK")
        (field (name "DB_APPROVED_BY") "VSN")
      )
      (libsource (lib "Database_Libs1") (part "LED"))
    )
    (comp (ref "D25")
      (value "Green  SML210MT ROHM")
      (footprint "SMD_0805_LED2012X100N")
      (fields
        (field (name "DB_PART_NUMBER") "OPT000000096")
        (field (name "DB_MANUFACTURER_PART") "KINGBRIGHT       KP-2012CGCK")
        (field (name "DB_VALUE") "KP-2012CGCK")
        (field (name "DB_APPROVED_BY") "VSN")
      )
      (libsource (lib "Database_Libs1") (part "LED"))
    )
    (comp (ref "D27")
      (value "Yellow SML210YT ROHM")
      (footprint "SMD_0805_LED2012X100N")
      (fields
        (field (name "DB_PART_NUMBER") "OPT000000092")
        (field (name "DB_MANUFACTURER_PART") "EVERLIGHT       17-21-Y2C-A0L1M2V0B-3T-AM")
        (field (name "DB_VALUE") "17-21-Y2C-A0L1M2V0B-3T-AM")
        (field (name "DB_APPROVED_BY") "VSN")
      )
      (libsource (lib "Database_Libs1") (part "LED"))
    )
    (comp (ref "D29")
      (value "Yellow SML210YT ROHM")
      (footprint "SMD_0805_LED2012X100N")
      (fields
        (field (name "DB_PART_NUMBER") "OPT000000092")
        (field (name "DB_MANUFACTURER_PART") "EVERLIGHT       17-21-Y2C-A0L1M2V0B-3T-AM")
        (field (name "DB_VALUE") "17-21-Y2C-A0L1M2V0B-3T-AM")
        (field (name "DB_APPROVED_BY") "VSN")
      )
      (libsource (lib "Database_Libs1") (part "LED"))
    )
    (comp (ref "D31")
      (value "Orange  SML210DT ROHM")
      (footprint "SMD_0805_LED2012X100N")
      (fields
        (field (name "DB_PART_NUMBER") "OPT000000096")
        (field (name "DB_MANUFACTURER_PART") "KINGBRIGHT       KP-2012CGCK")
        (field (name "DB_APPROVED_BY") "VSN")
      )
      (libsource (lib "altium-import") (part "root_0_LED_Orange_"))
    )
    (comp (ref "D33")
      (value "Red SML210VT ROHM")
      (footprint "SMD_0805_LED2012X100N")
      (fields
        (field (name "DB_PART_NUMBER") "OPT000000095")
        (field (name "DB_MANUFACTURER_PART") "KINGBRIGHT       KP-2012EC")
        (field (name "DB_VALUE") "KP-2012EC")
        (field (name "DB_APPROVED_BY") "VSN")
      )
      (libsource (lib "Database_Libs1") (part "LED"))
    )
    (comp (ref "D34")
      (value "Red SML210VT ROHM")
      (footprint "SMD_0805_LED2012X100N")
      (fields
        (field (name "DB_PART_NUMBER") "OPT000000095")
        (field (name "DB_MANUFACTURER_PART") "KINGBRIGHT       KP-2012EC")
        (field (name "DB_VALUE") "KP-2012EC")
        (field (name "DB_APPROVED_BY") "VSN")
      )
      (libsource (lib "Database_Libs1") (part "LED"))
    )
    (comp (ref "D35")
      (value "Green  SML210MT ROHM")
      (footprint "SMD_0805_LED2012X100N")
      (fields
        (field (name "DB_PART_NUMBER") "OPT000000096")
        (field (name "DB_MANUFACTURER_PART") "KINGBRIGHT       KP-2012CGCK")
        (field (name "DB_VALUE") "KP-2012CGCK")
        (field (name "DB_APPROVED_BY") "VSN")
      )
      (libsource (lib "Database_Libs1") (part "LED"))
    )
    (comp (ref "D36")
      (value "Green  SML210MT ROHM")
      (footprint "SMD_0805_LED2012X100N")
      (fields
        (field (name "DB_PART_NUMBER") "OPT000000096")
        (field (name "DB_MANUFACTURER_PART") "KINGBRIGHT       KP-2012CGCK")
        (field (name "DB_VALUE") "KP-2012CGCK")
        (field (name "DB_APPROVED_BY") "VSN")
      )
      (libsource (lib "Database_Libs1") (part "LED"))
    )
    (comp (ref "D37")
      (value "Yellow SML210YT ROHM")
      (footprint "SMD_0805_LED2012X100N")
      (fields
        (field (name "DB_PART_NUMBER") "OPT000000092")
        (field (name "DB_MANUFACTURER_PART") "EVERLIGHT       17-21-Y2C-A0L1M2V0B-3T-AM")
        (field (name "DB_VALUE") "17-21-Y2C-A0L1M2V0B-3T-AM")
        (field (name "DB_APPROVED_BY") "VSN")
      )
      (libsource (lib "Database_Libs1") (part "LED"))
    )
    (comp (ref "D38")
      (value "Yellow SML210YT ROHM")
      (footprint "SMD_0805_LED2012X100N")
      (fields
        (field (name "DB_PART_NUMBER") "OPT000000092")
        (field (name "DB_MANUFACTURER_PART") "EVERLIGHT       17-21-Y2C-A0L1M2V0B-3T-AM")
        (field (name "DB_VALUE") "17-21-Y2C-A0L1M2V0B-3T-AM")
        (field (name "DB_APPROVED_BY") "VSN")
      )
      (libsource (lib "Database_Libs1") (part "LED"))
    )
    (comp (ref "D39")
      (value "Orange  SML210DT ROHM")
      (footprint "SMD_0805_LED2012X100N")
      (fields
        (field (name "DB_PART_NUMBER") "OPT000000096")
        (field (name "DB_MANUFACTURER_PART") "KINGBRIGHT       KP-2012CGCK")
        (field (name "DB_APPROVED_BY") "VSN")
      )
      (libsource (lib "altium-import") (part "root_0_LED_Orange_"))
    )
    (comp (ref "D40")
      (value "Red SML210VT ROHM")
      (footprint "SMD_0805_LED2012X100N")
      (fields
        (field (name "DB_PART_NUMBER") "OPT000000095")
        (field (name "DB_MANUFACTURER_PART") "KINGBRIGHT       KP-2012EC")
        (field (name "DB_VALUE") "KP-2012EC")
        (field (name "DB_APPROVED_BY") "VSN")
      )
      (libsource (lib "Database_Libs1") (part "LED"))
    )
    (comp (ref "D41")
      (value "Red SML210VT ROHM")
      (footprint "SMD_0805_LED2012X100N")
      (fields
        (field (name "DB_PART_NUMBER") "OPT000000095")
        (field (name "DB_MANUFACTURER_PART") "KINGBRIGHT       KP-2012EC")
        (field (name "DB_VALUE") "KP-2012EC")
        (field (name "DB_APPROVED_BY") "VSN")
      )
      (libsource (lib "Database_Libs1") (part "LED"))
    )
    (comp (ref "D42")
      (value "Green  SML210MT ROHM")
      (footprint "SMD_0805_LED2012X100N")
      (fields
        (field (name "DB_PART_NUMBER") "OPT000000096")
        (field (name "DB_MANUFACTURER_PART") "KINGBRIGHT       KP-2012CGCK")
        (field (name "DB_VALUE") "KP-2012CGCK")
        (field (name "DB_APPROVED_BY") "VSN")
      )
      (libsource (lib "Database_Libs1") (part "LED"))
    )
    (comp (ref "D43")
      (value "Green  SML210MT ROHM")
      (footprint "SMD_0805_LED2012X100N")
      (fields
        (field (name "DB_PART_NUMBER") "OPT000000096")
        (field (name "DB_MANUFACTURER_PART") "KINGBRIGHT       KP-2012CGCK")
        (field (name "DB_VALUE") "KP-2012CGCK")
        (field (name "DB_APPROVED_BY") "VSN")
      )
      (libsource (lib "Database_Libs1") (part "LED"))
    )
    (comp (ref "D44")
      (value "Yellow SML210YT ROHM")
      (footprint "SMD_0805_LED2012X100N")
      (fields
        (field (name "DB_PART_NUMBER") "OPT000000092")
        (field (name "DB_MANUFACTURER_PART") "EVERLIGHT       17-21-Y2C-A0L1M2V0B-3T-AM")
        (field (name "DB_VALUE") "17-21-Y2C-A0L1M2V0B-3T-AM")
        (field (name "DB_APPROVED_BY") "VSN")
      )
      (libsource (lib "Database_Libs1") (part "LED"))
    )
    (comp (ref "D45")
      (value "Yellow SML210YT ROHM")
      (footprint "SMD_0805_LED2012X100N")
      (fields
        (field (name "DB_PART_NUMBER") "OPT000000092")
        (field (name "DB_MANUFACTURER_PART") "EVERLIGHT       17-21-Y2C-A0L1M2V0B-3T-AM")
        (field (name "DB_VALUE") "17-21-Y2C-A0L1M2V0B-3T-AM")
        (field (name "DB_APPROVED_BY") "VSN")
      )
      (libsource (lib "Database_Libs1") (part "LED"))
    )
    (comp (ref "D46")
      (value "Orange  SML210DT ROHM")
      (footprint "SMD_0805_LED2012X100N")
      (fields
        (field (name "DB_PART_NUMBER") "OPT000000096")
        (field (name "DB_MANUFACTURER_PART") "KINGBRIGHT       KP-2012CGCK")
        (field (name "DB_APPROVED_BY") "VSN")
      )
      (libsource (lib "altium-import") (part "root_0_LED_Orange_"))
    )
    (comp (ref "R1")
      (value "R")
      (footprint "SMD_0603_RESC1608X55N")
      (fields
        (field (name "DB_PART_NUMBER") "RES000006349")
        (field (name "DB_VALUE") "0R")
        (field (name "DB_TOLERANCE") "5%")
        (field (name "DB_MANUFACTURER_PART") "YAGEO    RC0603JR-070R")
        (field (name "DB_APPROVED_BY") "ISHIDDEN=T")
      )
      (libsource (lib "Database_Libs1") (part "R"))
    )
    (comp (ref "R2")
      (value "R")
      (footprint "SMD_0603_RESC1608X55N")
      (fields
        (field (name "DB_PART_NUMBER") "RES000006349")
        (field (name "DB_VALUE") "0R")
        (field (name "DB_TOLERANCE") "5%")
        (field (name "DB_MANUFACTURER_PART") "YAGEO    RC0603JR-070R")
        (field (name "DB_APPROVED_BY") "ISHIDDEN=T")
      )
      (libsource (lib "Database_Libs1") (part "R"))
    )
    (comp (ref "R3")
      (value "R")
      (footprint "SMD_0603_RESC1608X55N")
      (fields
        (field (name "DB_PART_NUMBER") "RES000006349")
        (field (name "DB_VALUE") "0R")
        (field (name "DB_TOLERANCE") "5%")
        (field (name "DB_MANUFACTURER_PART") "YAGEO    RC0603JR-070R")
        (field (name "DB_APPROVED_BY") "ISHIDDEN=T")
      )
      (libsource (lib "Database_Libs1") (part "R"))
    )
    (comp (ref "R19")
      (value "R")
      (footprint "SMD_0603_RESC1608X55N")
      (fields
        (field (name "DB_PART_NUMBER") "RES000006349")
        (field (name "DB_VALUE") "0R")
        (field (name "DB_TOLERANCE") "5%")
        (field (name "DB_MANUFACTURER_PART") "YAGEO    RC0603JR-070R")
        (field (name "DB_APPROVED_BY") "ISHIDDEN=T")
      )
      (libsource (lib "Database_Libs1") (part "R"))
    )
    (comp (ref "R25")
      (value "R")
      (footprint "SMD_0603_RESC1608X55N")
      (fields
        (field (name "DB_PART_NUMBER") "RES000006349")
        (field (name "DB_VALUE") "0R")
        (field (name "DB_TOLERANCE") "5%")
        (field (name "DB_MANUFACTURER_PART") "YAGEO    RC0603JR-070R")
        (field (name "DB_APPROVED_BY") "ISHIDDEN=T")
      )
      (libsource (lib "Database_Libs1") (part "R"))
    )
    (comp (ref "R37")
      (value "R")
      (footprint "SMD_0603_RESC1608X55N")
      (fields
        (field (name "DB_PART_NUMBER") "RES000006349")
        (field (name "DB_VALUE") "0R")
        (field (name "DB_TOLERANCE") "5%")
        (field (name "DB_MANUFACTURER_PART") "YAGEO    RC0603JR-070R")
        (field (name "DB_APPROVED_BY") "ISHIDDEN=T")
      )
      (libsource (lib "Database_Libs1") (part "R"))
    )
    (comp (ref "R38")
      (value "R")
      (footprint "SMD_0603_RESC1608X55N")
      (fields
        (field (name "DB_PART_NUMBER") "RES000006349")
        (field (name "DB_VALUE") "0R")
        (field (name "DB_TOLERANCE") "5%")
        (field (name "DB_MANUFACTURER_PART") "YAGEO    RC0603JR-070R")
        (field (name "DB_APPROVED_BY") "ISHIDDEN=T")
      )
      (libsource (lib "Database_Libs1") (part "R"))
    )
    (comp (ref "R39")
      (value "R")
      (footprint "SMD_0603_RESC1608X55N")
      (fields
        (field (name "DB_PART_NUMBER") "RES000006349")
        (field (name "DB_VALUE") "0R")
        (field (name "DB_TOLERANCE") "5%")
        (field (name "DB_MANUFACTURER_PART") "YAGEO    RC0603JR-070R")
        (field (name "DB_APPROVED_BY") "ISHIDDEN=T")
      )
      (libsource (lib "Database_Libs1") (part "R"))
    )
    (comp (ref "R40")
      (value "R")
      (footprint "SMD_0603_RESC1608X55N")
      (fields
        (field (name "DB_PART_NUMBER") "RES000006349")
        (field (name "DB_VALUE") "0R")
        (field (name "DB_TOLERANCE") "5%")
        (field (name "DB_MANUFACTURER_PART") "YAGEO    RC0603JR-070R")
        (field (name "DB_APPROVED_BY") "ISHIDDEN=T")
      )
      (libsource (lib "Database_Libs1") (part "R"))
    )
    (comp (ref "R41")
      (value "R")
      (footprint "SMD_0603_RESC1608X55N")
      (fields
        (field (name "DB_PART_NUMBER") "RES000006349")
        (field (name "DB_VALUE") "0R")
        (field (name "DB_TOLERANCE") "5%")
        (field (name "DB_MANUFACTURER_PART") "YAGEO    RC0603JR-070R")
        (field (name "DB_APPROVED_BY") "ISHIDDEN=T")
      )
      (libsource (lib "Database_Libs1") (part "R"))
    )
    (comp (ref "R42")
      (value "R")
      (footprint "SMD_0603_RESC1608X55N")
      (fields
        (field (name "DB_PART_NUMBER") "RES000006349")
        (field (name "DB_VALUE") "0R")
        (field (name "DB_TOLERANCE") "5%")
        (field (name "DB_MANUFACTURER_PART") "YAGEO    RC0603JR-070R")
        (field (name "DB_APPROVED_BY") "ISHIDDEN=T")
      )
      (libsource (lib "Database_Libs1") (part "R"))
    )
    (comp (ref "TP1")
      (value "TEST_POINT_1")
      (footprint "SMD_TP_100-254")
      (fields
        (field (name "DB_PART_NUMBER") "TPO000000001")
        (field (name "DB_MANUFACTURER_PART") "ISHIDDEN=T")
        (field (name "DB_APPROVED_BY") "ISHIDDEN=T")
      )
      (libsource (lib "Database_Libs1") (part "TEST_POINT_1"))
    )
    (comp (ref "TP3")
      (value "TEST_POINT_1")
      (footprint "SMD_TP_100-254")
      (fields
        (field (name "DB_PART_NUMBER") "TPO000000001")
        (field (name "DB_MANUFACTURER_PART") "ISHIDDEN=T")
        (field (name "DB_APPROVED_BY") "ISHIDDEN=T")
      )
      (libsource (lib "Database_Libs1") (part "TEST_POINT_1"))
    )
    (comp (ref "TP4")
      (value "TEST_POINT_1")
      (footprint "SMD_TP_100-254")
      (fields
        (field (name "DB_PART_NUMBER") "TPO000000001")
        (field (name "DB_MANUFACTURER_PART") "ISHIDDEN=T")
        (field (name "DB_APPROVED_BY") "ISHIDDEN=T")
      )
      (libsource (lib "Database_Libs1") (part "TEST_POINT_1"))
    )
    (comp (ref "TP8")
      (value "TEST_POINT_1")
      (footprint "SMD_TP_100-254")
      (fields
        (field (name "DB_PART_NUMBER") "TPO000000001")
        (field (name "DB_MANUFACTURER_PART") "ISHIDDEN=T")
        (field (name "DB_APPROVED_BY") "ISHIDDEN=T")
      )
      (libsource (lib "Database_Libs1") (part "TEST_POINT_1"))
    )
    (comp (ref "TP9")
      (value "TEST_POINT_1")
      (footprint "SMD_TP_100-254")
      (fields
        (field (name "DB_PART_NUMBER") "TPO000000001")
        (field (name "DB_MANUFACTURER_PART") "ISHIDDEN=T")
        (field (name "DB_APPROVED_BY") "ISHIDDEN=T")
      )
      (libsource (lib "Database_Libs1") (part "TEST_POINT_1"))
    )
    (comp (ref "TP14")
      (value "TEST_POINT_1")
      (footprint "SMD_TP_100-254")
      (fields
        (field (name "DB_PART_NUMBER") "TPO000000001")
        (field (name "DB_MANUFACTURER_PART") "ISHIDDEN=T")
        (field (name "DB_APPROVED_BY") "ISHIDDEN=T")
      )
      (libsource (lib "Database_Libs1") (part "TEST_POINT_1"))
    )
    (comp (ref "TP15")
      (value "TEST_POINT_1")
      (footprint "SMD_TP_100-254")
      (fields
        (field (name "DB_PART_NUMBER") "TPO000000001")
        (field (name "DB_MANUFACTURER_PART") "ISHIDDEN=T")
        (field (name "DB_APPROVED_BY") "ISHIDDEN=T")
      )
      (libsource (lib "Database_Libs1") (part "TEST_POINT_1"))
    )
    (comp (ref "TP16")
      (value "TEST_POINT_1")
      (footprint "SMD_TP_100-254")
      (fields
        (field (name "DB_PART_NUMBER") "TPO000000001")
        (field (name "DB_MANUFACTURER_PART") "ISHIDDEN=T")
        (field (name "DB_APPROVED_BY") "ISHIDDEN=T")
      )
      (libsource (lib "Database_Libs1") (part "TEST_POINT_1"))
    )
    (comp (ref "U2")
      (value "Minion 99s256")
      (footprint "SMD_BGA900C80P30X30")
      (libsource (lib "Schlib1") (part "Minion 99s256"))
    )
    (comp (ref "U3")
      (value "Minion 99s256")
      (footprint "SMD_BGA900C80P30X30")
      (libsource (lib "Schlib1") (part "Minion 99s256"))
    )
    (comp (ref "U4")
      (value "Minion 99s256")
      (footprint "SMD_BGA900C80P30X30")
      (libsource (lib "Schlib1") (part "Minion 99s256"))
    )
    (comp (ref "U13")
      (value "Minion 99s256")
      (footprint "SMD_BGA900C80P30X30")
      (libsource (lib "Schlib1") (part "Minion 99s256"))
    )
    (comp (ref "YO1")
      (value "(OPT)XTAL_TXC 16 MHz_DFN_2X2.5MM")
      (footprint "SMD_OSCCF200X250X90-4N")
      (libsource (lib "Schlib1") (part "SMD_OSC_DFN_2X2.5MM"))
    )
    (comp (ref "YO2")
      (value "XTAL_TXC 16 MHz_DFN_2.5X3.2MM")
      (footprint "SMD_OSCCF250X320X90-4N")
      (libsource (lib "Schlib1") (part "SMD_OSC_DFN_2.5X3.2MM"))
    )
    (comp (ref "YO3")
      (value "(OPT)XTAL_TXC 16 MHz_DFN_3.2x5mm")
      (footprint "SMD_OSCCF320X400X90-4N")
      (libsource (lib "Schlib1") (part "SMD_OSC_DFN_3.2x5mm"))
    )
    (comp (ref "YO4")
      (value "(OPT)XTAL_TXC 16 MHz_DFN_2X2.5MM")
      (footprint "SMD_OSCCF200X250X90-4N")
      (libsource (lib "Schlib1") (part "SMD_OSC_DFN_2X2.5MM"))
    )
    (comp (ref "YO5")
      (value "XTAL_TXC 16 MHz_DFN_2.5X3.2MM")
      (footprint "SMD_OSCCF250X320X90-4N")
      (libsource (lib "Schlib1") (part "SMD_OSC_DFN_2.5X3.2MM"))
    )
    (comp (ref "YO6")
      (value "(OPT)XTAL_TXC 16 MHz_DFN_3.2x5mm")
      (footprint "SMD_OSCCF320X400X90-4N")
      (libsource (lib "Schlib1") (part "SMD_OSC_DFN_3.2x5mm"))
    )
    (comp (ref "YO7")
      (value "(OPT)XTAL_TXC 16 MHz_TA 7x5mm")
      (footprint "SMD_OSCCC500X700X100-4N")
      (libsource (lib "Schlib1") (part "SMD_OSC_TA 7x5mm"))
    )
    (comp (ref "YO8")
      (value "(OPT)XTAL_TXC 16 MHz_TA 7x5mm")
      (footprint "SMD_OSCCC500X700X100-4N")
      (libsource (lib "Schlib1") (part "SMD_OSC_TA 7x5mm"))
    )
    (comp (ref "YO9")
      (value "(OPT)XTAL_TXC 16 MHz_DFN_2X2.5MM")
      (footprint "SMD_OSCCF200X250X90-4N")
      (libsource (lib "Schlib1") (part "SMD_OSC_DFN_2X2.5MM"))
    )
    (comp (ref "YO10")
      (value "XTAL_TXC 16 MHz_DFN_2.5X3.2MM")
      (footprint "SMD_OSCCF250X320X90-4N")
      (libsource (lib "Schlib1") (part "SMD_OSC_DFN_2.5X3.2MM"))
    )
    (comp (ref "YO11")
      (value "(OPT)XTAL_TXC 16 MHz_DFN_2X2.5MM")
      (footprint "SMD_OSCCF200X250X90-4N")
      (libsource (lib "Schlib1") (part "SMD_OSC_DFN_2X2.5MM"))
    )
    (comp (ref "YO12")
      (value "XTAL_TXC 16 MHz_DFN_2.5X3.2MM")
      (footprint "SMD_OSCCF250X320X90-4N")
      (libsource (lib "Schlib1") (part "SMD_OSC_DFN_2.5X3.2MM"))
    )
    (comp (ref "YO13")
      (value "(OPT)XTAL_TXC 16 MHz_DFN_3.2x5mm")
      (footprint "SMD_OSCCF320X400X90-4N")
      (libsource (lib "Schlib1") (part "SMD_OSC_DFN_3.2x5mm"))
    )
    (comp (ref "YO14")
      (value "(OPT)XTAL_TXC 16 MHz_TA 7x5mm")
      (footprint "SMD_OSCCC500X700X100-4N")
      (libsource (lib "Schlib1") (part "SMD_OSC_TA 7x5mm"))
    )
    (comp (ref "YO15")
      (value "(OPT)XTAL_TXC 16 MHz_DFN_3.2x5mm")
      (footprint "SMD_OSCCF320X400X90-4N")
      (libsource (lib "Schlib1") (part "SMD_OSC_DFN_3.2x5mm"))
    )
    (comp (ref "YO16")
      (value "(OPT)XTAL_TXC 16 MHz_TA 7x5mm")
      (footprint "SMD_OSCCC500X700X100-4N")
      (libsource (lib "Schlib1") (part "SMD_OSC_TA 7x5mm"))
    )
  )
  (nets
    (net (code "1") (name "/0.9V") (class "Default")
      (node (ref "C304") (pin "2") (pinfunction "2_2") (pintype "passive"))
      (node (ref "C305") (pin "2") (pinfunction "2_2") (pintype "passive"))
      (node (ref "C306") (pin "2") (pinfunction "2_2") (pintype "passive"))
      (node (ref "C307") (pin "2") (pinfunction "2_2") (pintype "passive"))
      (node (ref "U13") (pin "AJ16") (pinfunction "PLL_AVDD2_AJ16") (pintype "passive"))
      (node (ref "U2") (pin "AJ16") (pinfunction "PLL_AVDD2_AJ16") (pintype "passive"))
      (node (ref "U3") (pin "AJ16") (pinfunction "PLL_AVDD2_AJ16") (pintype "passive"))
      (node (ref "U4") (pin "AJ16") (pinfunction "PLL_AVDD2_AJ16") (pintype "passive"))
    )
    (net (code "2") (name "/1.8V") (class "Default")
      (node (ref "C289") (pin "2") (pinfunction "2_2") (pintype "passive"))
      (node (ref "C291") (pin "2") (pinfunction "2_2") (pintype "passive"))
      (node (ref "C293") (pin "2") (pinfunction "2_2") (pintype "passive"))
      (node (ref "C294") (pin "2") (pinfunction "2_2") (pintype "passive"))
      (node (ref "U13") (pin "AJ12") (pinfunction "TSHUT_AVDD18_AJ12") (pintype "passive"))
      (node (ref "U13") (pin "AJ15") (pinfunction "PLL_AVDD_AJ15") (pintype "passive"))
      (node (ref "U13") (pin "AK13") (pinfunction "POR_AVDD18_AK13") (pintype "passive"))
      (node (ref "U2") (pin "AJ12") (pinfunction "TSHUT_AVDD18_AJ12") (pintype "passive"))
      (node (ref "U2") (pin "AJ15") (pinfunction "PLL_AVDD_AJ15") (pintype "passive"))
      (node (ref "U2") (pin "AK13") (pinfunction "POR_AVDD18_AK13") (pintype "passive"))
      (node (ref "U3") (pin "AJ12") (pinfunction "TSHUT_AVDD18_AJ12") (pintype "passive"))
      (node (ref "U3") (pin "AJ15") (pinfunction "PLL_AVDD_AJ15") (pintype "passive"))
      (node (ref "U3") (pin "AK13") (pinfunction "POR_AVDD18_AK13") (pintype "passive"))
      (node (ref "U4") (pin "AJ12") (pinfunction "TSHUT_AVDD18_AJ12") (pintype "passive"))
      (node (ref "U4") (pin "AJ15") (pinfunction "PLL_AVDD_AJ15") (pintype "passive"))
      (node (ref "U4") (pin "AK13") (pinfunction "POR_AVDD18_AK13") (pintype "passive"))
    )
    (net (code "3") (name "/1V") (class "Default")
      (node (ref "C106") (pin "2") (pinfunction "2_2") (pintype "passive"))
      (node (ref "C107") (pin "2") (pinfunction "2_2") (pintype "passive"))
      (node (ref "C108") (pin "2") (pinfunction "2_2") (pintype "passive"))
      (node (ref "C109") (pin "2") (pinfunction "2_2") (pintype "passive"))
      (node (ref "C110") (pin "2") (pinfunction "2_2") (pintype "passive"))
      (node (ref "C111") (pin "2") (pinfunction "2_2") (pintype "passive"))
      (node (ref "C112") (pin "2") (pinfunction "2_2") (pintype "passive"))
      (node (ref "C113") (pin "2") (pinfunction "2_2") (pintype "passive"))
      (node (ref "C114") (pin "2") (pinfunction "2_2") (pintype "passive"))
      (node (ref "C115") (pin "2") (pinfunction "2_2") (pintype "passive"))
      (node (ref "C118") (pin "2") (pinfunction "2_2") (pintype "passive"))
      (node (ref "C119") (pin "2") (pinfunction "2_2") (pintype "passive"))
      (node (ref "C122") (pin "2") (pinfunction "2_2") (pintype "passive"))
      (node (ref "C123") (pin "2") (pinfunction "2_2") (pintype "passive"))
      (node (ref "C126") (pin "2") (pinfunction "2_2") (pintype "passive"))
      (node (ref "C127") (pin "2") (pinfunction "2_2") (pintype "passive"))
      (node (ref "C138") (pin "2") (pinfunction "2_2") (pintype "passive"))
      (node (ref "C139") (pin "2") (pinfunction "2_2") (pintype "passive"))
      (node (ref "C140") (pin "2") (pinfunction "2_2") (pintype "passive"))
      (node (ref "C141") (pin "2") (pinfunction "2_2") (pintype "passive"))
      (node (ref "C142") (pin "2") (pinfunction "2_2") (pintype "passive"))
      (node (ref "C143") (pin "2") (pinfunction "2_2") (pintype "passive"))
      (node (ref "C144") (pin "2") (pinfunction "2_2") (pintype "passive"))
      (node (ref "C145") (pin "2") (pinfunction "2_2") (pintype "passive"))
      (node (ref "C146") (pin "2") (pinfunction "2_2") (pintype "passive"))
      (node (ref "C147") (pin "2") (pinfunction "2_2") (pintype "passive"))
      (node (ref "C148") (pin "2") (pinfunction "2_2") (pintype "passive"))
      (node (ref "C149") (pin "2") (pinfunction "2_2") (pintype "passive"))
      (node (ref "C150") (pin "2") (pinfunction "2_2") (pintype "passive"))
      (node (ref "C151") (pin "2") (pinfunction "2_2") (pintype "passive"))
      (node (ref "C152") (pin "2") (pinfunction "2_2") (pintype "passive"))
      (node (ref "C153") (pin "2") (pinfunction "2_2") (pintype "passive"))
      (node (ref "C154") (pin "2") (pinfunction "2_2") (pintype "passive"))
      (node (ref "C155") (pin "2") (pinfunction "2_2") (pintype "passive"))
      (node (ref "C156") (pin "2") (pinfunction "2_2") (pintype "passive"))
      (node (ref "C157") (pin "2") (pinfunction "2_2") (pintype "passive"))
      (node (ref "C158") (pin "2") (pinfunction "2_2") (pintype "passive"))
      (node (ref "C159") (pin "2") (pinfunction "2_2") (pintype "passive"))
      (node (ref "C160") (pin "2") (pinfunction "2_2") (pintype "passive"))
      (node (ref "C161") (pin "2") (pinfunction "2_2") (pintype "passive"))
      (node (ref "C162") (pin "2") (pinfunction "2_2") (pintype "passive"))
      (node (ref "C163") (pin "2") (pinfunction "2_2") (pintype "passive"))
      (node (ref "C164") (pin "2") (pinfunction "2_2") (pintype "passive"))
      (node (ref "C165") (pin "2") (pinfunction "2_2") (pintype "passive"))
      (node (ref "C166") (pin "2") (pinfunction "2_2") (pintype "passive"))
      (node (ref "C167") (pin "2") (pinfunction "2_2") (pintype "passive"))
      (node (ref "C169") (pin "2") (pinfunction "2_2") (pintype "passive"))
      (node (ref "C170") (pin "2") (pinfunction "2_2") (pintype "passive"))
      (node (ref "C171") (pin "2") (pinfunction "2_2") (pintype "passive"))
      (node (ref "C172") (pin "2") (pinfunction "2_2") (pintype "passive"))
      (node (ref "C173") (pin "2") (pinfunction "2_2") (pintype "passive"))
      (node (ref "C174") (pin "2") (pinfunction "2_2") (pintype "passive"))
      (node (ref "C175") (pin "2") (pinfunction "2_2") (pintype "passive"))
      (node (ref "C176") (pin "2") (pinfunction "2_2") (pintype "passive"))
      (node (ref "C177") (pin "2") (pinfunction "2_2") (pintype "passive"))
      (node (ref "C178") (pin "2") (pinfunction "2_2") (pintype "passive"))
      (node (ref "C179") (pin "2") (pinfunction "2_2") (pintype "passive"))
      (node (ref "C180") (pin "2") (pinfunction "2_2") (pintype "passive"))
      (node (ref "C19") (pin "2") (pinfunction "2_2") (pintype "passive"))
      (node (ref "C197") (pin "2") (pinfunction "2_2") (pintype "passive"))
      (node (ref "C198") (pin "2") (pinfunction "2_2") (pintype "passive"))
      (node (ref "C199") (pin "2") (pinfunction "2_2") (pintype "passive"))
      (node (ref "C200") (pin "2") (pinfunction "2_2") (pintype "passive"))
      (node (ref "C201") (pin "2") (pinfunction "2_2") (pintype "passive"))
      (node (ref "C202") (pin "2") (pinfunction "2_2") (pintype "passive"))
      (node (ref "C203") (pin "2") (pinfunction "2_2") (pintype "passive"))
      (node (ref "C204") (pin "2") (pinfunction "2_2") (pintype "passive"))
      (node (ref "C205") (pin "2") (pinfunction "2_2") (pintype "passive"))
      (node (ref "C206") (pin "2") (pinfunction "2_2") (pintype "passive"))
      (node (ref "C207") (pin "2") (pinfunction "2_2") (pintype "passive"))
      (node (ref "C208") (pin "2") (pinfunction "2_2") (pintype "passive"))
      (node (ref "C209") (pin "2") (pinfunction "2_2") (pintype "passive"))
      (node (ref "C210") (pin "2") (pinfunction "2_2") (pintype "passive"))
      (node (ref "C211") (pin "2") (pinfunction "2_2") (pintype "passive"))
      (node (ref "C212") (pin "2") (pinfunction "2_2") (pintype "passive"))
      (node (ref "C213") (pin "2") (pinfunction "2_2") (pintype "passive"))
      (node (ref "C214") (pin "2") (pinfunction "2_2") (pintype "passive"))
      (node (ref "C22") (pin "2") (pinfunction "2_2") (pintype "passive"))
      (node (ref "C23") (pin "2") (pinfunction "2_2") (pintype "passive"))
      (node (ref "C239") (pin "2") (pinfunction "2_2") (pintype "passive"))
      (node (ref "C26") (pin "2") (pinfunction "2_2") (pintype "passive"))
      (node (ref "C27") (pin "2") (pinfunction "2_2") (pintype "passive"))
      (node (ref "C30") (pin "2") (pinfunction "2_2") (pintype "passive"))
      (node (ref "C31") (pin "2") (pinfunction "2_2") (pintype "passive"))
      (node (ref "C36") (pin "2") (pinfunction "2_2") (pintype "passive"))
      (node (ref "C42") (pin "2") (pinfunction "2_2") (pintype "passive"))
      (node (ref "C43") (pin "2") (pinfunction "2_2") (pintype "passive"))
      (node (ref "C44") (pin "2") (pinfunction "2_2") (pintype "passive"))
      (node (ref "C45") (pin "2") (pinfunction "2_2") (pintype "passive"))
      (node (ref "C46") (pin "2") (pinfunction "2_2") (pintype "passive"))
      (node (ref "C47") (pin "2") (pinfunction "2_2") (pintype "passive"))
      (node (ref "C48") (pin "2") (pinfunction "2_2") (pintype "passive"))
      (node (ref "C49") (pin "2") (pinfunction "2_2") (pintype "passive"))
      (node (ref "C50") (pin "2") (pinfunction "2_2") (pintype "passive"))
      (node (ref "C51") (pin "2") (pinfunction "2_2") (pintype "passive"))
      (node (ref "C54") (pin "2") (pinfunction "2_2") (pintype "passive"))
      (node (ref "C55") (pin "2") (pinfunction "2_2") (pintype "passive"))
      (node (ref "C58") (pin "2") (pinfunction "2_2") (pintype "passive"))
      (node (ref "C59") (pin "2") (pinfunction "2_2") (pintype "passive"))
      (node (ref "C62") (pin "2") (pinfunction "2_2") (pintype "passive"))
      (node (ref "C63") (pin "2") (pinfunction "2_2") (pintype "passive"))
      (node (ref "C74") (pin "2") (pinfunction "2_2") (pintype "passive"))
      (node (ref "C75") (pin "2") (pinfunction "2_2") (pintype "passive"))
      (node (ref "C76") (pin "2") (pinfunction "2_2") (pintype "passive"))
      (node (ref "C77") (pin "2") (pinfunction "2_2") (pintype "passive"))
      (node (ref "C78") (pin "2") (pinfunction "2_2") (pintype "passive"))
      (node (ref "C79") (pin "2") (pinfunction "2_2") (pintype "passive"))
      (node (ref "C80") (pin "2") (pinfunction "2_2") (pintype "passive"))
      (node (ref "C81") (pin "2") (pinfunction "2_2") (pintype "passive"))
      (node (ref "C82") (pin "2") (pinfunction "2_2") (pintype "passive"))
      (node (ref "C83") (pin "2") (pinfunction "2_2") (pintype "passive"))
      (node (ref "C86") (pin "2") (pinfunction "2_2") (pintype "passive"))
      (node (ref "C87") (pin "2") (pinfunction "2_2") (pintype "passive"))
      (node (ref "C90") (pin "2") (pinfunction "2_2") (pintype "passive"))
      (node (ref "C91") (pin "2") (pinfunction "2_2") (pintype "passive"))
      (node (ref "C94") (pin "2") (pinfunction "2_2") (pintype "passive"))
      (node (ref "C95") (pin "2") (pinfunction "2_2") (pintype "passive"))
    )
    (net (code "4") (name "/3.3V") (class "Default")
      (node (ref "C303") (pin "2") (pinfunction "2_2") (pintype "passive"))
      (node (ref "C309") (pin "2") (pinfunction "2_2") (pintype "passive"))
      (node (ref "C315") (pin "2") (pinfunction "2_2") (pintype "passive"))
      (node (ref "C322") (pin "1") (pinfunction "1_1") (pintype "passive"))
      (node (ref "C604") (pin "1") (pinfunction "1_1") (pintype "passive"))
      (node (ref "C609") (pin "1") (pinfunction "1_1") (pintype "passive"))
      (node (ref "C610") (pin "1") (pinfunction "1_1") (pintype "passive"))
      (node (ref "C616") (pin "2") (pinfunction "2_2") (pintype "passive"))
      (node (ref "U13") (pin "AJ19") (pinfunction "IO_VDD_AJ19") (pintype "passive"))
      (node (ref "U13") (pin "AJ23") (pinfunction "IO_VDD_AJ23") (pintype "passive"))
      (node (ref "U13") (pin "AK10") (pinfunction "IO_VDD_AK10") (pintype "passive"))
      (node (ref "U13") (pin "AK4") (pinfunction "IO_VDD_AK4") (pintype "passive"))
      (node (ref "U13") (pin "AK6") (pinfunction "IO_VDD_AK6") (pintype "passive"))
      (node (ref "U2") (pin "AJ19") (pinfunction "IO_VDD_AJ19") (pintype "passive"))
      (node (ref "U2") (pin "AJ20") (pinfunction "CHIP_ADDR0_AJ20") (pintype "passive"))
      (node (ref "U2") (pin "AJ23") (pinfunction "IO_VDD_AJ23") (pintype "passive"))
      (node (ref "U2") (pin "AK10") (pinfunction "IO_VDD_AK10") (pintype "passive"))
      (node (ref "U2") (pin "AK4") (pinfunction "IO_VDD_AK4") (pintype "passive"))
      (node (ref "U2") (pin "AK6") (pinfunction "IO_VDD_AK6") (pintype "passive"))
      (node (ref "U3") (pin "AJ19") (pinfunction "IO_VDD_AJ19") (pintype "passive"))
      (node (ref "U3") (pin "AJ23") (pinfunction "IO_VDD_AJ23") (pintype "passive"))
      (node (ref "U3") (pin "AK10") (pinfunction "IO_VDD_AK10") (pintype "passive"))
      (node (ref "U3") (pin "AK21") (pinfunction "CHIP_ADDR1_AK21") (pintype "passive"))
      (node (ref "U3") (pin "AK4") (pinfunction "IO_VDD_AK4") (pintype "passive"))
      (node (ref "U3") (pin "AK6") (pinfunction "IO_VDD_AK6") (pintype "passive"))
      (node (ref "U4") (pin "AJ19") (pinfunction "IO_VDD_AJ19") (pintype "passive"))
      (node (ref "U4") (pin "AJ20") (pinfunction "CHIP_ADDR0_AJ20") (pintype "passive"))
      (node (ref "U4") (pin "AJ23") (pinfunction "IO_VDD_AJ23") (pintype "passive"))
      (node (ref "U4") (pin "AK10") (pinfunction "IO_VDD_AK10") (pintype "passive"))
      (node (ref "U4") (pin "AK21") (pinfunction "CHIP_ADDR1_AK21") (pintype "passive"))
      (node (ref "U4") (pin "AK4") (pinfunction "IO_VDD_AK4") (pintype "passive"))
      (node (ref "U4") (pin "AK6") (pinfunction "IO_VDD_AK6") (pintype "passive"))
      (node (ref "YO1") (pin "1") (pinfunction "OE_1") (pintype "passive"))
      (node (ref "YO1") (pin "4") (pinfunction "VDD_4") (pintype "passive"))
      (node (ref "YO10") (pin "1") (pinfunction "OE_1") (pintype "passive"))
      (node (ref "YO10") (pin "4") (pinfunction "VDD_4") (pintype "passive"))
      (node (ref "YO11") (pin "1") (pinfunction "OE_1") (pintype "passive"))
      (node (ref "YO11") (pin "4") (pinfunction "VDD_4") (pintype "passive"))
      (node (ref "YO12") (pin "1") (pinfunction "OE_1") (pintype "passive"))
      (node (ref "YO12") (pin "4") (pinfunction "VDD_4") (pintype "passive"))
      (node (ref "YO13") (pin "1") (pinfunction "OE_1") (pintype "passive"))
      (node (ref "YO13") (pin "4") (pinfunction "VDD_4") (pintype "passive"))
      (node (ref "YO14") (pin "1") (pinfunction "OE_1") (pintype "passive"))
      (node (ref "YO14") (pin "4") (pinfunction "VDD_4") (pintype "passive"))
      (node (ref "YO15") (pin "1") (pinfunction "OE_1") (pintype "passive"))
      (node (ref "YO15") (pin "4") (pinfunction "VDD_4") (pintype "passive"))
      (node (ref "YO16") (pin "1") (pinfunction "OE_1") (pintype "passive"))
      (node (ref "YO16") (pin "4") (pinfunction "VDD_4") (pintype "passive"))
      (node (ref "YO2") (pin "1") (pinfunction "OE_1") (pintype "passive"))
      (node (ref "YO2") (pin "4") (pinfunction "VDD_4") (pintype "passive"))
      (node (ref "YO3") (pin "1") (pinfunction "OE_1") (pintype "passive"))
      (node (ref "YO3") (pin "4") (pinfunction "VDD_4") (pintype "passive"))
      (node (ref "YO4") (pin "1") (pinfunction "OE_1") (pintype "passive"))
      (node (ref "YO4") (pin "4") (pinfunction "VDD_4") (pintype "passive"))
      (node (ref "YO5") (pin "1") (pinfunction "OE_1") (pintype "passive"))
      (node (ref "YO5") (pin "4") (pinfunction "VDD_4") (pintype "passive"))
      (node (ref "YO6") (pin "1") (pinfunction "OE_1") (pintype "passive"))
      (node (ref "YO6") (pin "4") (pinfunction "VDD_4") (pintype "passive"))
      (node (ref "YO7") (pin "1") (pinfunction "OE_1") (pintype "passive"))
      (node (ref "YO7") (pin "4") (pinfunction "VDD_4") (pintype "passive"))
      (node (ref "YO8") (pin "1") (pinfunction "OE_1") (pintype "passive"))
      (node (ref "YO8") (pin "4") (pinfunction "VDD_4") (pintype "passive"))
      (node (ref "YO9") (pin "1") (pinfunction "OE_1") (pintype "passive"))
      (node (ref "YO9") (pin "4") (pinfunction "VDD_4") (pintype "passive"))
    )
    (net (code "5") (name "/INT_OUT1") (class "Default")
      (node (ref "TP1") (pin "1") (pinfunction "1_1") (pintype "passive"))
      (node (ref "U13") (pin "AK24") (pinfunction "INT_OUT_AK24") (pintype "passive"))
    )
    (net (code "6") (name "/INT_OUT2") (class "Default")
      (node (ref "TP3") (pin "1") (pinfunction "1_1") (pintype "passive"))
      (node (ref "U2") (pin "AK24") (pinfunction "INT_OUT_AK24") (pintype "passive"))
    )
    (net (code "7") (name "/INT_OUT3") (class "Default")
      (node (ref "TP4") (pin "1") (pinfunction "1_1") (pintype "passive"))
      (node (ref "U3") (pin "AK24") (pinfunction "INT_OUT_AK24") (pintype "passive"))
    )
    (net (code "8") (name "/INT_OUT4") (class "Default")
      (node (ref "TP8") (pin "1") (pinfunction "1_1") (pintype "passive"))
      (node (ref "U4") (pin "AK24") (pinfunction "INT_OUT_AK24") (pintype "passive"))
    )
    (net (code "9") (name "/LED_BUSY1") (class "Default")
      (node (ref "D12") (pin "2") (pinfunction "A_2") (pintype "passive"))
      (node (ref "U13") (pin "AK8") (pinfunction "LED_BUSY_AK8") (pintype "passive"))
    )
    (net (code "10") (name "/LED_BUSY2") (class "Default")
      (node (ref "D21") (pin "2") (pinfunction "A_2") (pintype "passive"))
      (node (ref "U2") (pin "AK8") (pinfunction "LED_BUSY_AK8") (pintype "passive"))
    )
    (net (code "11") (name "/LED_BUSY3") (class "Default")
      (node (ref "D34") (pin "2") (pinfunction "A_2") (pintype "passive"))
      (node (ref "U3") (pin "AK8") (pinfunction "LED_BUSY_AK8") (pintype "passive"))
    )
    (net (code "12") (name "/LED_BUSY4") (class "Default")
      (node (ref "D41") (pin "2") (pinfunction "A_2") (pintype "passive"))
      (node (ref "U4") (pin "AK8") (pinfunction "LED_BUSY_AK8") (pintype "passive"))
    )
    (net (code "13") (name "/LED_CLK1") (class "Default")
      (node (ref "D16") (pin "2") (pinfunction "A_2") (pintype "passive"))
      (node (ref "U13") (pin "AK5") (pinfunction "LED_CLK_AK5") (pintype "passive"))
    )
    (net (code "14") (name "/LED_CLK2") (class "Default")
      (node (ref "D29") (pin "2") (pinfunction "A_2") (pintype "passive"))
      (node (ref "U2") (pin "AK5") (pinfunction "LED_CLK_AK5") (pintype "passive"))
    )
    (net (code "15") (name "/LED_CLK3") (class "Default")
      (node (ref "D38") (pin "2") (pinfunction "A_2") (pintype "passive"))
      (node (ref "U3") (pin "AK5") (pinfunction "LED_CLK_AK5") (pintype "passive"))
    )
    (net (code "16") (name "/LED_CLK4") (class "Default")
      (node (ref "D45") (pin "2") (pinfunction "A_2") (pintype "passive"))
      (node (ref "U4") (pin "AK5") (pinfunction "LED_CLK_AK5") (pintype "passive"))
    )
    (net (code "17") (name "/LED_HOT1") (class "Default")
      (node (ref "D9") (pin "2") (pinfunction "A_2") (pintype "passive"))
      (node (ref "U13") (pin "AJ7") (pinfunction "LED_HOT_AJ7") (pintype "passive"))
    )
    (net (code "18") (name "/LED_HOT2") (class "Default")
      (node (ref "D27") (pin "2") (pinfunction "A_2") (pintype "passive"))
      (node (ref "U2") (pin "AJ7") (pinfunction "LED_HOT_AJ7") (pintype "passive"))
    )
    (net (code "19") (name "/LED_HOT3") (class "Default")
      (node (ref "D37") (pin "2") (pinfunction "A_2") (pintype "passive"))
      (node (ref "U3") (pin "AJ7") (pinfunction "LED_HOT_AJ7") (pintype "passive"))
    )
    (net (code "20") (name "/LED_HOT4") (class "Default")
      (node (ref "D44") (pin "2") (pinfunction "A_2") (pintype "passive"))
      (node (ref "U4") (pin "AJ7") (pinfunction "LED_HOT_AJ7") (pintype "passive"))
    )
    (net (code "21") (name "/LED_IDLE1") (class "Default")
      (node (ref "D5") (pin "2") (pinfunction "A_2") (pintype "passive"))
      (node (ref "U13") (pin "AJ8") (pinfunction "LED_IDLE_AJ8") (pintype "passive"))
    )
    (net (code "22") (name "/LED_IDLE2") (class "Default")
      (node (ref "D20") (pin "2") (pinfunction "A_2") (pintype "passive"))
      (node (ref "U2") (pin "AJ8") (pinfunction "LED_IDLE_AJ8") (pintype "passive"))
    )
    (net (code "23") (name "/LED_IDLE3") (class "Default")
      (node (ref "D33") (pin "2") (pinfunction "A_2") (pintype "passive"))
      (node (ref "U3") (pin "AJ8") (pinfunction "LED_IDLE_AJ8") (pintype "passive"))
    )
    (net (code "24") (name "/LED_IDLE4") (class "Default")
      (node (ref "D40") (pin "2") (pinfunction "A_2") (pintype "passive"))
      (node (ref "U4") (pin "AJ8") (pinfunction "LED_IDLE_AJ8") (pintype "passive"))
    )
    (net (code "25") (name "/LED_NONCE1") (class "Default")
      (node (ref "D17") (pin "2") (pinfunction "A_2") (pintype "passive"))
      (node (ref "U13") (pin "AK7") (pinfunction "LED_NONCE_AK7") (pintype "passive"))
    )
    (net (code "26") (name "/LED_NONCE2") (class "Default")
      (node (ref "D31") (pin "2") (pinfunction "A_2") (pintype "passive"))
      (node (ref "U2") (pin "AK7") (pinfunction "LED_NONCE_AK7") (pintype "passive"))
    )
    (net (code "27") (name "/LED_NONCE3") (class "Default")
      (node (ref "D39") (pin "2") (pinfunction "A_2") (pintype "passive"))
      (node (ref "U3") (pin "AK7") (pinfunction "LED_NONCE_AK7") (pintype "passive"))
    )
    (net (code "28") (name "/LED_NONCE4") (class "Default")
      (node (ref "D46") (pin "2") (pinfunction "A_2") (pintype "passive"))
      (node (ref "U4") (pin "AK7") (pinfunction "LED_NONCE_AK7") (pintype "passive"))
    )
    (net (code "29") (name "/LED_POWER1") (class "Default")
      (node (ref "D13") (pin "2") (pinfunction "A_2") (pintype "passive"))
      (node (ref "U13") (pin "AK9") (pinfunction "LED_POWER_AK9") (pintype "passive"))
    )
    (net (code "30") (name "/LED_POWER2") (class "Default")
      (node (ref "D25") (pin "2") (pinfunction "A_2") (pintype "passive"))
      (node (ref "U2") (pin "AK9") (pinfunction "LED_POWER_AK9") (pintype "passive"))
    )
    (net (code "31") (name "/LED_POWER3") (class "Default")
      (node (ref "D36") (pin "2") (pinfunction "A_2") (pintype "passive"))
      (node (ref "U3") (pin "AK9") (pinfunction "LED_POWER_AK9") (pintype "passive"))
    )
    (net (code "32") (name "/LED_POWER4") (class "Default")
      (node (ref "D43") (pin "2") (pinfunction "A_2") (pintype "passive"))
      (node (ref "U4") (pin "AK9") (pinfunction "LED_POWER_AK9") (pintype "passive"))
    )
    (net (code "33") (name "/LED_SPI1") (class "Default")
      (node (ref "D7") (pin "2") (pinfunction "A_2") (pintype "passive"))
      (node (ref "U13") (pin "AJ5") (pinfunction "LED_SPI_AJ5") (pintype "passive"))
    )
    (net (code "34") (name "/LED_SPI2") (class "Default")
      (node (ref "D24") (pin "2") (pinfunction "A_2") (pintype "passive"))
      (node (ref "U2") (pin "AJ5") (pinfunction "LED_SPI_AJ5") (pintype "passive"))
    )
    (net (code "35") (name "/LED_SPI3") (class "Default")
      (node (ref "D35") (pin "2") (pinfunction "A_2") (pintype "passive"))
      (node (ref "U3") (pin "AJ5") (pinfunction "LED_SPI_AJ5") (pintype "passive"))
    )
    (net (code "36") (name "/LED_SPI4") (class "Default")
      (node (ref "D42") (pin "2") (pinfunction "A_2") (pintype "passive"))
      (node (ref "U4") (pin "AJ5") (pinfunction "LED_SPI_AJ5") (pintype "passive"))
    )
    (net (code "37") (name "/POR_IOVSEL1") (class "Default")
      (node (ref "R19") (pin "2") (pinfunction "2_2") (pintype "passive"))
      (node (ref "U13") (pin "AJ13") (pinfunction "POR_IOVSEL_AJ13") (pintype "passive"))
    )
    (net (code "38") (name "/POR_IOVSEL2") (class "Default")
      (node (ref "R37") (pin "2") (pinfunction "2_2") (pintype "passive"))
      (node (ref "U2") (pin "AJ13") (pinfunction "POR_IOVSEL_AJ13") (pintype "passive"))
    )
    (net (code "39") (name "/POR_IOVSEL3") (class "Default")
      (node (ref "R39") (pin "2") (pinfunction "2_2") (pintype "passive"))
      (node (ref "U3") (pin "AJ13") (pinfunction "POR_IOVSEL_AJ13") (pintype "passive"))
    )
    (net (code "40") (name "/POR_IOVSEL4") (class "Default")
      (node (ref "R40") (pin "2") (pinfunction "2_2") (pintype "passive"))
      (node (ref "U4") (pin "AJ13") (pinfunction "POR_IOVSEL_AJ13") (pintype "passive"))
    )
    (net (code "41") (name "/RESET_ASIC") (class "Default")
      (node (ref "C594") (pin "1") (pinfunction "1_1") (pintype "passive"))
      (node (ref "C595") (pin "1") (pinfunction "1_1") (pintype "passive"))
      (node (ref "C597") (pin "1") (pinfunction "1_1") (pintype "passive"))
      (node (ref "C601") (pin "1") (pinfunction "1_1") (pintype "passive"))
      (node (ref "U13") (pin "AK28") (pinfunction "RSTN_IN_AK28") (pintype "passive"))
      (node (ref "U2") (pin "AK28") (pinfunction "RSTN_IN_AK28") (pintype "passive"))
      (node (ref "U3") (pin "AK28") (pinfunction "RSTN_IN_AK28") (pintype "passive"))
      (node (ref "U4") (pin "AK28") (pinfunction "RSTN_IN_AK28") (pintype "passive"))
    )
    (net (code "42") (name "/SPI_CS") (class "Default")
      (node (ref "U13") (pin "AJ25") (pinfunction "SPI_CSN_AJ25") (pintype "passive"))
      (node (ref "U2") (pin "AJ25") (pinfunction "SPI_CSN_AJ25") (pintype "passive"))
      (node (ref "U3") (pin "AJ25") (pinfunction "SPI_CSN_AJ25") (pintype "passive"))
      (node (ref "U4") (pin "AJ25") (pinfunction "SPI_CSN_AJ25") (pintype "passive"))
    )
    (net (code "43") (name "/SPI_MISO") (class "Default")
      (node (ref "U13") (pin "AJ24") (pinfunction "SPI_MISO_AJ24") (pintype "passive"))
      (node (ref "U2") (pin "AJ24") (pinfunction "SPI_MISO_AJ24") (pintype "passive"))
      (node (ref "U3") (pin "AJ24") (pinfunction "SPI_MISO_AJ24") (pintype "passive"))
      (node (ref "U4") (pin "AJ24") (pinfunction "SPI_MISO_AJ24") (pintype "passive"))
    )
    (net (code "44") (name "/SPI_MOSI") (class "Default")
      (node (ref "U13") (pin "AK25") (pinfunction "SPI_MOSI_AK25") (pintype "passive"))
      (node (ref "U2") (pin "AK25") (pinfunction "SPI_MOSI_AK25") (pintype "passive"))
      (node (ref "U3") (pin "AK25") (pinfunction "SPI_MOSI_AK25") (pintype "passive"))
      (node (ref "U4") (pin "AK25") (pinfunction "SPI_MOSI_AK25") (pintype "passive"))
    )
    (net (code "45") (name "/SPI_SCK") (class "Default")
      (node (ref "U13") (pin "AK27") (pinfunction "SPI_CLK_AK27") (pintype "passive"))
      (node (ref "U2") (pin "AK27") (pinfunction "SPI_CLK_AK27") (pintype "passive"))
      (node (ref "U3") (pin "AK27") (pinfunction "SPI_CLK_AK27") (pintype "passive"))
      (node (ref "U4") (pin "AK27") (pinfunction "SPI_CLK_AK27") (pintype "passive"))
    )
    (net (code "46") (name "/TEST_MODE1") (class "Default")
      (node (ref "R25") (pin "2") (pinfunction "2_2") (pintype "passive"))
      (node (ref "U13") (pin "AK3") (pinfunction "TEST_MODE_AK3") (pintype "passive"))
    )
    (net (code "47") (name "/TEST_MODE2") (class "Default")
      (node (ref "R38") (pin "2") (pinfunction "2_2") (pintype "passive"))
      (node (ref "U2") (pin "AK3") (pinfunction "TEST_MODE_AK3") (pintype "passive"))
    )
    (net (code "48") (name "/TEST_MODE3") (class "Default")
      (node (ref "R41") (pin "2") (pinfunction "2_2") (pintype "passive"))
      (node (ref "U3") (pin "AK3") (pinfunction "TEST_MODE_AK3") (pintype "passive"))
    )
    (net (code "49") (name "/TEST_MODE4") (class "Default")
      (node (ref "R42") (pin "2") (pinfunction "2_2") (pintype "passive"))
      (node (ref "U4") (pin "AK3") (pinfunction "TEST_MODE_AK3") (pintype "passive"))
    )
    (net (code "50") (name "/XCLK1") (class "Default")
      (node (ref "R1") (pin "1") (pinfunction "1_1") (pintype "passive"))
      (node (ref "U13") (pin "AK19") (pinfunction "XTAL12M_IN_AK19") (pintype "passive"))
      (node (ref "YO4") (pin "3") (pinfunction "OSC_3") (pintype "passive"))
      (node (ref "YO5") (pin "3") (pinfunction "OSC_3") (pintype "passive"))
      (node (ref "YO6") (pin "3") (pinfunction "OSC_3") (pintype "passive"))
      (node (ref "YO7") (pin "3") (pinfunction "OSC_3") (pintype "passive"))
    )
    (net (code "51") (name "/XCLK2") (class "Default")
      (node (ref "R1") (pin "2") (pinfunction "2_2") (pintype "passive"))
      (node (ref "R2") (pin "1") (pinfunction "1_1") (pintype "passive"))
      (node (ref "U2") (pin "AK19") (pinfunction "XTAL12M_IN_AK19") (pintype "passive"))
      (node (ref "YO1") (pin "3") (pinfunction "OSC_3") (pintype "passive"))
      (node (ref "YO2") (pin "3") (pinfunction "OSC_3") (pintype "passive"))
      (node (ref "YO3") (pin "3") (pinfunction "OSC_3") (pintype "passive"))
      (node (ref "YO8") (pin "3") (pinfunction "OSC_3") (pintype "passive"))
    )
    (net (code "52") (name "/XCLK3") (class "Default")
      (node (ref "R2") (pin "2") (pinfunction "2_2") (pintype "passive"))
      (node (ref "R3") (pin "1") (pinfunction "1_1") (pintype "passive"))
      (node (ref "U3") (pin "AK19") (pinfunction "XTAL12M_IN_AK19") (pintype "passive"))
      (node (ref "YO10") (pin "3") (pinfunction "OSC_3") (pintype "passive"))
      (node (ref "YO13") (pin "3") (pinfunction "OSC_3") (pintype "passive"))
      (node (ref "YO14") (pin "3") (pinfunction "OSC_3") (pintype "passive"))
      (node (ref "YO9") (pin "3") (pinfunction "OSC_3") (pintype "passive"))
    )
    (net (code "53") (name "/XCLK4") (class "Default")
      (node (ref "R3") (pin "2") (pinfunction "2_2") (pintype "passive"))
      (node (ref "U4") (pin "AK19") (pinfunction "XTAL12M_IN_AK19") (pintype "passive"))
      (node (ref "YO11") (pin "3") (pinfunction "OSC_3") (pintype "passive"))
      (node (ref "YO12") (pin "3") (pinfunction "OSC_3") (pintype "passive"))
      (node (ref "YO15") (pin "3") (pinfunction "OSC_3") (pintype "passive"))
      (node (ref "YO16") (pin "3") (pinfunction "OSC_3") (pintype "passive"))
    )
    (net (code "54") (name "/XCLK_OUT1") (class "Default")
      (node (ref "TP9") (pin "1") (pinfunction "1_1") (pintype "passive"))
      (node (ref "U13") (pin "AK18") (pinfunction "XTAL12M_OUT_AK18") (pintype "passive"))
    )
    (net (code "55") (name "/XCLK_OUT2") (class "Default")
      (node (ref "TP14") (pin "1") (pinfunction "1_1") (pintype "passive"))
      (node (ref "U2") (pin "AK18") (pinfunction "XTAL12M_OUT_AK18") (pintype "passive"))
    )
    (net (code "56") (name "/XCLK_OUT3") (class "Default")
      (node (ref "TP15") (pin "1") (pinfunction "1_1") (pintype "passive"))
      (node (ref "U3") (pin "AK18") (pinfunction "XTAL12M_OUT_AK18") (pintype "passive"))
    )
    (net (code "57") (name "/XCLK_OUT4") (class "Default")
      (node (ref "TP16") (pin "1") (pinfunction "1_1") (pintype "passive"))
      (node (ref "U4") (pin "AK18") (pinfunction "XTAL12M_OUT_AK18") (pintype "passive"))
    )
    (net (code "58") (name "GND") (class "Default")
      (node (ref "C106") (pin "1") (pinfunction "1_1") (pintype "passive"))
      (node (ref "C107") (pin "1") (pinfunction "1_1") (pintype "passive"))
      (node (ref "C108") (pin "1") (pinfunction "1_1") (pintype "passive"))
      (node (ref "C109") (pin "1") (pinfunction "1_1") (pintype "passive"))
      (node (ref "C110") (pin "1") (pinfunction "1_1") (pintype "passive"))
      (node (ref "C111") (pin "1") (pinfunction "1_1") (pintype "passive"))
      (node (ref "C112") (pin "1") (pinfunction "1_1") (pintype "passive"))
      (node (ref "C113") (pin "1") (pinfunction "1_1") (pintype "passive"))
      (node (ref "C114") (pin "1") (pinfunction "1_1") (pintype "passive"))
      (node (ref "C115") (pin "1") (pinfunction "1_1") (pintype "passive"))
      (node (ref "C118") (pin "1") (pinfunction "1_1") (pintype "passive"))
      (node (ref "C119") (pin "1") (pinfunction "1_1") (pintype "passive"))
      (node (ref "C122") (pin "1") (pinfunction "1_1") (pintype "passive"))
      (node (ref "C123") (pin "1") (pinfunction "1_1") (pintype "passive"))
      (node (ref "C126") (pin "1") (pinfunction "1_1") (pintype "passive"))
      (node (ref "C127") (pin "1") (pinfunction "1_1") (pintype "passive"))
      (node (ref "C138") (pin "1") (pinfunction "1_1") (pintype "passive"))
      (node (ref "C139") (pin "1") (pinfunction "1_1") (pintype "passive"))
      (node (ref "C140") (pin "1") (pinfunction "1_1") (pintype "passive"))
      (node (ref "C141") (pin "1") (pinfunction "1_1") (pintype "passive"))
      (node (ref "C142") (pin "1") (pinfunction "1_1") (pintype "passive"))
      (node (ref "C143") (pin "1") (pinfunction "1_1") (pintype "passive"))
      (node (ref "C144") (pin "1") (pinfunction "1_1") (pintype "passive"))
      (node (ref "C145") (pin "1") (pinfunction "1_1") (pintype "passive"))
      (node (ref "C146") (pin "1") (pinfunction "1_1") (pintype "passive"))
      (node (ref "C147") (pin "1") (pinfunction "1_1") (pintype "passive"))
      (node (ref "C148") (pin "1") (pinfunction "1_1") (pintype "passive"))
      (node (ref "C149") (pin "1") (pinfunction "1_1") (pintype "passive"))
      (node (ref "C150") (pin "1") (pinfunction "1_1") (pintype "passive"))
      (node (ref "C151") (pin "1") (pinfunction "1_1") (pintype "passive"))
      (node (ref "C152") (pin "1") (pinfunction "1_1") (pintype "passive"))
      (node (ref "C153") (pin "1") (pinfunction "1_1") (pintype "passive"))
      (node (ref "C154") (pin "1") (pinfunction "1_1") (pintype "passive"))
      (node (ref "C155") (pin "1") (pinfunction "1_1") (pintype "passive"))
      (node (ref "C156") (pin "1") (pinfunction "1_1") (pintype "passive"))
      (node (ref "C157") (pin "1") (pinfunction "1_1") (pintype "passive"))
      (node (ref "C158") (pin "1") (pinfunction "1_1") (pintype "passive"))
      (node (ref "C159") (pin "1") (pinfunction "1_1") (pintype "passive"))
      (node (ref "C160") (pin "1") (pinfunction "1_1") (pintype "passive"))
      (node (ref "C161") (pin "1") (pinfunction "1_1") (pintype "passive"))
      (node (ref "C162") (pin "1") (pinfunction "1_1") (pintype "passive"))
      (node (ref "C163") (pin "1") (pinfunction "1_1") (pintype "passive"))
      (node (ref "C164") (pin "1") (pinfunction "1_1") (pintype "passive"))
      (node (ref "C165") (pin "1") (pinfunction "1_1") (pintype "passive"))
      (node (ref "C166") (pin "1") (pinfunction "1_1") (pintype "passive"))
      (node (ref "C167") (pin "1") (pinfunction "1_1") (pintype "passive"))
      (node (ref "C169") (pin "1") (pinfunction "1_1") (pintype "passive"))
      (node (ref "C170") (pin "1") (pinfunction "1_1") (pintype "passive"))
      (node (ref "C171") (pin "1") (pinfunction "1_1") (pintype "passive"))
      (node (ref "C172") (pin "1") (pinfunction "1_1") (pintype "passive"))
      (node (ref "C173") (pin "1") (pinfunction "1_1") (pintype "passive"))
      (node (ref "C174") (pin "1") (pinfunction "1_1") (pintype "passive"))
      (node (ref "C175") (pin "1") (pinfunction "1_1") (pintype "passive"))
      (node (ref "C176") (pin "1") (pinfunction "1_1") (pintype "passive"))
      (node (ref "C177") (pin "1") (pinfunction "1_1") (pintype "passive"))
      (node (ref "C178") (pin "1") (pinfunction "1_1") (pintype "passive"))
      (node (ref "C179") (pin "1") (pinfunction "1_1") (pintype "passive"))
      (node (ref "C180") (pin "1") (pinfunction "1_1") (pintype "passive"))
      (node (ref "C19") (pin "1") (pinfunction "1_1") (pintype "passive"))
      (node (ref "C197") (pin "1") (pinfunction "1_1") (pintype "passive"))
      (node (ref "C198") (pin "1") (pinfunction "1_1") (pintype "passive"))
      (node (ref "C199") (pin "1") (pinfunction "1_1") (pintype "passive"))
      (node (ref "C200") (pin "1") (pinfunction "1_1") (pintype "passive"))
      (node (ref "C201") (pin "1") (pinfunction "1_1") (pintype "passive"))
      (node (ref "C202") (pin "1") (pinfunction "1_1") (pintype "passive"))
      (node (ref "C203") (pin "1") (pinfunction "1_1") (pintype "passive"))
      (node (ref "C204") (pin "1") (pinfunction "1_1") (pintype "passive"))
      (node (ref "C205") (pin "1") (pinfunction "1_1") (pintype "passive"))
      (node (ref "C206") (pin "1") (pinfunction "1_1") (pintype "passive"))
      (node (ref "C207") (pin "1") (pinfunction "1_1") (pintype "passive"))
      (node (ref "C208") (pin "1") (pinfunction "1_1") (pintype "passive"))
      (node (ref "C209") (pin "1") (pinfunction "1_1") (pintype "passive"))
      (node (ref "C210") (pin "1") (pinfunction "1_1") (pintype "passive"))
      (node (ref "C211") (pin "1") (pinfunction "1_1") (pintype "passive"))
      (node (ref "C212") (pin "1") (pinfunction "1_1") (pintype "passive"))
      (node (ref "C213") (pin "1") (pinfunction "1_1") (pintype "passive"))
      (node (ref "C214") (pin "1") (pinfunction "1_1") (pintype "passive"))
      (node (ref "C22") (pin "1") (pinfunction "1_1") (pintype "passive"))
      (node (ref "C23") (pin "1") (pinfunction "1_1") (pintype "passive"))
      (node (ref "C239") (pin "1") (pinfunction "1_1") (pintype "passive"))
      (node (ref "C26") (pin "1") (pinfunction "1_1") (pintype "passive"))
      (node (ref "C27") (pin "1") (pinfunction "1_1") (pintype "passive"))
      (node (ref "C289") (pin "1") (pinfunction "1_1") (pintype "passive"))
      (node (ref "C291") (pin "1") (pinfunction "1_1") (pintype "passive"))
      (node (ref "C293") (pin "1") (pinfunction "1_1") (pintype "passive"))
      (node (ref "C294") (pin "1") (pinfunction "1_1") (pintype "passive"))
      (node (ref "C30") (pin "1") (pinfunction "1_1") (pintype "passive"))
      (node (ref "C303") (pin "1") (pinfunction "1_1") (pintype "passive"))
      (node (ref "C304") (pin "1") (pinfunction "1_1") (pintype "passive"))
      (node (ref "C305") (pin "1") (pinfunction "1_1") (pintype "passive"))
      (node (ref "C306") (pin "1") (pinfunction "1_1") (pintype "passive"))
      (node (ref "C307") (pin "1") (pinfunction "1_1") (pintype "passive"))
      (node (ref "C309") (pin "1") (pinfunction "1_1") (pintype "passive"))
      (node (ref "C31") (pin "1") (pinfunction "1_1") (pintype "passive"))
      (node (ref "C315") (pin "1") (pinfunction "1_1") (pintype "passive"))
      (node (ref "C322") (pin "2") (pinfunction "2_2") (pintype "passive"))
      (node (ref "C36") (pin "1") (pinfunction "1_1") (pintype "passive"))
      (node (ref "C42") (pin "1") (pinfunction "1_1") (pintype "passive"))
      (node (ref "C43") (pin "1") (pinfunction "1_1") (pintype "passive"))
      (node (ref "C44") (pin "1") (pinfunction "1_1") (pintype "passive"))
      (node (ref "C45") (pin "1") (pinfunction "1_1") (pintype "passive"))
      (node (ref "C46") (pin "1") (pinfunction "1_1") (pintype "passive"))
      (node (ref "C47") (pin "1") (pinfunction "1_1") (pintype "passive"))
      (node (ref "C48") (pin "1") (pinfunction "1_1") (pintype "passive"))
      (node (ref "C49") (pin "1") (pinfunction "1_1") (pintype "passive"))
      (node (ref "C50") (pin "1") (pinfunction "1_1") (pintype "passive"))
      (node (ref "C51") (pin "1") (pinfunction "1_1") (pintype "passive"))
      (node (ref "C54") (pin "1") (pinfunction "1_1") (pintype "passive"))
      (node (ref "C55") (pin "1") (pinfunction "1_1") (pintype "passive"))
      (node (ref "C58") (pin "1") (pinfunction "1_1") (pintype "passive"))
      (node (ref "C59") (pin "1") (pinfunction "1_1") (pintype "passive"))
      (node (ref "C594") (pin "2") (pinfunction "2_2") (pintype "passive"))
      (node (ref "C595") (pin "2") (pinfunction "2_2") (pintype "passive"))
      (node (ref "C597") (pin "2") (pinfunction "2_2") (pintype "passive"))
      (node (ref "C601") (pin "2") (pinfunction "2_2") (pintype "passive"))
      (node (ref "C604") (pin "2") (pinfunction "2_2") (pintype "passive"))
      (node (ref "C609") (pin "2") (pinfunction "2_2") (pintype "passive"))
      (node (ref "C610") (pin "2") (pinfunction "2_2") (pintype "passive"))
      (node (ref "C616") (pin "1") (pinfunction "1_1") (pintype "passive"))
      (node (ref "C62") (pin "1") (pinfunction "1_1") (pintype "passive"))
      (node (ref "C63") (pin "1") (pinfunction "1_1") (pintype "passive"))
      (node (ref "C74") (pin "1") (pinfunction "1_1") (pintype "passive"))
      (node (ref "C75") (pin "1") (pinfunction "1_1") (pintype "passive"))
      (node (ref "C76") (pin "1") (pinfunction "1_1") (pintype "passive"))
      (node (ref "C77") (pin "1") (pinfunction "1_1") (pintype "passive"))
      (node (ref "C78") (pin "1") (pinfunction "1_1") (pintype "passive"))
      (node (ref "C79") (pin "1") (pinfunction "1_1") (pintype "passive"))
      (node (ref "C80") (pin "1") (pinfunction "1_1") (pintype "passive"))
      (node (ref "C81") (pin "1") (pinfunction "1_1") (pintype "passive"))
      (node (ref "C82") (pin "1") (pinfunction "1_1") (pintype "passive"))
      (node (ref "C83") (pin "1") (pinfunction "1_1") (pintype "passive"))
      (node (ref "C86") (pin "1") (pinfunction "1_1") (pintype "passive"))
      (node (ref "C87") (pin "1") (pinfunction "1_1") (pintype "passive"))
      (node (ref "C90") (pin "1") (pinfunction "1_1") (pintype "passive"))
      (node (ref "C91") (pin "1") (pinfunction "1_1") (pintype "passive"))
      (node (ref "C94") (pin "1") (pinfunction "1_1") (pintype "passive"))
      (node (ref "C95") (pin "1") (pinfunction "1_1") (pintype "passive"))
      (node (ref "D12") (pin "1") (pinfunction "C_1") (pintype "passive"))
      (node (ref "D13") (pin "1") (pinfunction "C_1") (pintype "passive"))
      (node (ref "D16") (pin "1") (pinfunction "C_1") (pintype "passive"))
      (node (ref "D17") (pin "1") (pinfunction "C_1") (pintype "passive"))
      (node (ref "D20") (pin "1") (pinfunction "C_1") (pintype "passive"))
      (node (ref "D21") (pin "1") (pinfunction "C_1") (pintype "passive"))
      (node (ref "D24") (pin "1") (pinfunction "C_1") (pintype "passive"))
      (node (ref "D25") (pin "1") (pinfunction "C_1") (pintype "passive"))
      (node (ref "D27") (pin "1") (pinfunction "C_1") (pintype "passive"))
      (node (ref "D29") (pin "1") (pinfunction "C_1") (pintype "passive"))
      (node (ref "D31") (pin "1") (pinfunction "C_1") (pintype "passive"))
      (node (ref "D33") (pin "1") (pinfunction "C_1") (pintype "passive"))
      (node (ref "D34") (pin "1") (pinfunction "C_1") (pintype "passive"))
      (node (ref "D35") (pin "1") (pinfunction "C_1") (pintype "passive"))
      (node (ref "D36") (pin "1") (pinfunction "C_1") (pintype "passive"))
      (node (ref "D37") (pin "1") (pinfunction "C_1") (pintype "passive"))
      (node (ref "D38") (pin "1") (pinfunction "C_1") (pintype "passive"))
      (node (ref "D39") (pin "1") (pinfunction "C_1") (pintype "passive"))
      (node (ref "D40") (pin "1") (pinfunction "C_1") (pintype "passive"))
      (node (ref "D41") (pin "1") (pinfunction "C_1") (pintype "passive"))
      (node (ref "D42") (pin "1") (pinfunction "C_1") (pintype "passive"))
      (node (ref "D43") (pin "1") (pinfunction "C_1") (pintype "passive"))
      (node (ref "D44") (pin "1") (pinfunction "C_1") (pintype "passive"))
      (node (ref "D45") (pin "1") (pinfunction "C_1") (pintype "passive"))
      (node (ref "D46") (pin "1") (pinfunction "C_1") (pintype "passive"))
      (node (ref "D5") (pin "1") (pinfunction "C_1") (pintype "passive"))
      (node (ref "D7") (pin "1") (pinfunction "C_1") (pintype "passive"))
      (node (ref "D9") (pin "1") (pinfunction "C_1") (pintype "passive"))
      (node (ref "R19") (pin "1") (pinfunction "1_1") (pintype "passive"))
      (node (ref "R25") (pin "1") (pinfunction "1_1") (pintype "passive"))
      (node (ref "R37") (pin "1") (pinfunction "1_1") (pintype "passive"))
      (node (ref "R38") (pin "1") (pinfunction "1_1") (pintype "passive"))
      (node (ref "R39") (pin "1") (pinfunction "1_1") (pintype "passive"))
      (node (ref "R40") (pin "1") (pinfunction "1_1") (pintype "passive"))
      (node (ref "R41") (pin "1") (pinfunction "1_1") (pintype "passive"))
      (node (ref "R42") (pin "1") (pinfunction "1_1") (pintype "passive"))
      (node (ref "U13") (pin "AJ20") (pinfunction "CHIP_ADDR0_AJ20") (pintype "passive"))
      (node (ref "U13") (pin "AJ21") (pinfunction "CHIP_ADDR2_AJ21") (pintype "passive"))
      (node (ref "U13") (pin "AJ22") (pinfunction "CHIP_ADDR4_AJ22") (pintype "passive"))
      (node (ref "U13") (pin "AJ26") (pinfunction "SPI_MODE_AJ26") (pintype "passive"))
      (node (ref "U13") (pin "AK11") (pinfunction "TSHUT_AGND18_AK11") (pintype "passive"))
      (node (ref "U13") (pin "AK12") (pinfunction "POR_AGND18_AK12") (pintype "passive"))
      (node (ref "U13") (pin "AK15") (pinfunction "PLL_AVSS_AK15") (pintype "passive"))
      (node (ref "U13") (pin "AK16") (pinfunction "PLL_AVSS2_AK16") (pintype "passive"))
      (node (ref "U13") (pin "AK21") (pinfunction "CHIP_ADDR1_AK21") (pintype "passive"))
      (node (ref "U13") (pin "AK22") (pinfunction "CHIP_ADDR3_AK22") (pintype "passive"))
      (node (ref "U2") (pin "AJ21") (pinfunction "CHIP_ADDR2_AJ21") (pintype "passive"))
      (node (ref "U2") (pin "AJ22") (pinfunction "CHIP_ADDR4_AJ22") (pintype "passive"))
      (node (ref "U2") (pin "AJ26") (pinfunction "SPI_MODE_AJ26") (pintype "passive"))
      (node (ref "U2") (pin "AK11") (pinfunction "TSHUT_AGND18_AK11") (pintype "passive"))
      (node (ref "U2") (pin "AK12") (pinfunction "POR_AGND18_AK12") (pintype "passive"))
      (node (ref "U2") (pin "AK15") (pinfunction "PLL_AVSS_AK15") (pintype "passive"))
      (node (ref "U2") (pin "AK16") (pinfunction "PLL_AVSS2_AK16") (pintype "passive"))
      (node (ref "U2") (pin "AK21") (pinfunction "CHIP_ADDR1_AK21") (pintype "passive"))
      (node (ref "U2") (pin "AK22") (pinfunction "CHIP_ADDR3_AK22") (pintype "passive"))
      (node (ref "U3") (pin "AJ20") (pinfunction "CHIP_ADDR0_AJ20") (pintype "passive"))
      (node (ref "U3") (pin "AJ21") (pinfunction "CHIP_ADDR2_AJ21") (pintype "passive"))
      (node (ref "U3") (pin "AJ22") (pinfunction "CHIP_ADDR4_AJ22") (pintype "passive"))
      (node (ref "U3") (pin "AJ26") (pinfunction "SPI_MODE_AJ26") (pintype "passive"))
      (node (ref "U3") (pin "AK11") (pinfunction "TSHUT_AGND18_AK11") (pintype "passive"))
      (node (ref "U3") (pin "AK12") (pinfunction "POR_AGND18_AK12") (pintype "passive"))
      (node (ref "U3") (pin "AK15") (pinfunction "PLL_AVSS_AK15") (pintype "passive"))
      (node (ref "U3") (pin "AK16") (pinfunction "PLL_AVSS2_AK16") (pintype "passive"))
      (node (ref "U3") (pin "AK22") (pinfunction "CHIP_ADDR3_AK22") (pintype "passive"))
      (node (ref "U4") (pin "AJ21") (pinfunction "CHIP_ADDR2_AJ21") (pintype "passive"))
      (node (ref "U4") (pin "AJ22") (pinfunction "CHIP_ADDR4_AJ22") (pintype "passive"))
      (node (ref "U4") (pin "AJ26") (pinfunction "SPI_MODE_AJ26") (pintype "passive"))
      (node (ref "U4") (pin "AK11") (pinfunction "TSHUT_AGND18_AK11") (pintype "passive"))
      (node (ref "U4") (pin "AK12") (pinfunction "POR_AGND18_AK12") (pintype "passive"))
      (node (ref "U4") (pin "AK15") (pinfunction "PLL_AVSS_AK15") (pintype "passive"))
      (node (ref "U4") (pin "AK16") (pinfunction "PLL_AVSS2_AK16") (pintype "passive"))
      (node (ref "U4") (pin "AK22") (pinfunction "CHIP_ADDR3_AK22") (pintype "passive"))
      (node (ref "YO1") (pin "2") (pinfunction "GND_2") (pintype "passive"))
      (node (ref "YO10") (pin "2") (pinfunction "GND_2") (pintype "passive"))
      (node (ref "YO11") (pin "2") (pinfunction "GND_2") (pintype "passive"))
      (node (ref "YO12") (pin "2") (pinfunction "GND_2") (pintype "passive"))
      (node (ref "YO13") (pin "2") (pinfunction "GND_2") (pintype "passive"))
      (node (ref "YO14") (pin "2") (pinfunction "GND_2") (pintype "passive"))
      (node (ref "YO15") (pin "2") (pinfunction "GND_2") (pintype "passive"))
      (node (ref "YO16") (pin "2") (pinfunction "GND_2") (pintype "passive"))
      (node (ref "YO2") (pin "2") (pinfunction "GND_2") (pintype "passive"))
      (node (ref "YO3") (pin "2") (pinfunction "GND_2") (pintype "passive"))
      (node (ref "YO4") (pin "2") (pinfunction "GND_2") (pintype "passive"))
      (node (ref "YO5") (pin "2") (pinfunction "GND_2") (pintype "passive"))
      (node (ref "YO6") (pin "2") (pinfunction "GND_2") (pintype "passive"))
      (node (ref "YO7") (pin "2") (pinfunction "GND_2") (pintype "passive"))
      (node (ref "YO8") (pin "2") (pinfunction "GND_2") (pintype "passive"))
      (node (ref "YO9") (pin "2") (pinfunction "GND_2") (pintype "passive"))
    )
  )
)
